# PCB.net
KiCad netlist of a schematic drawn in EAGLE
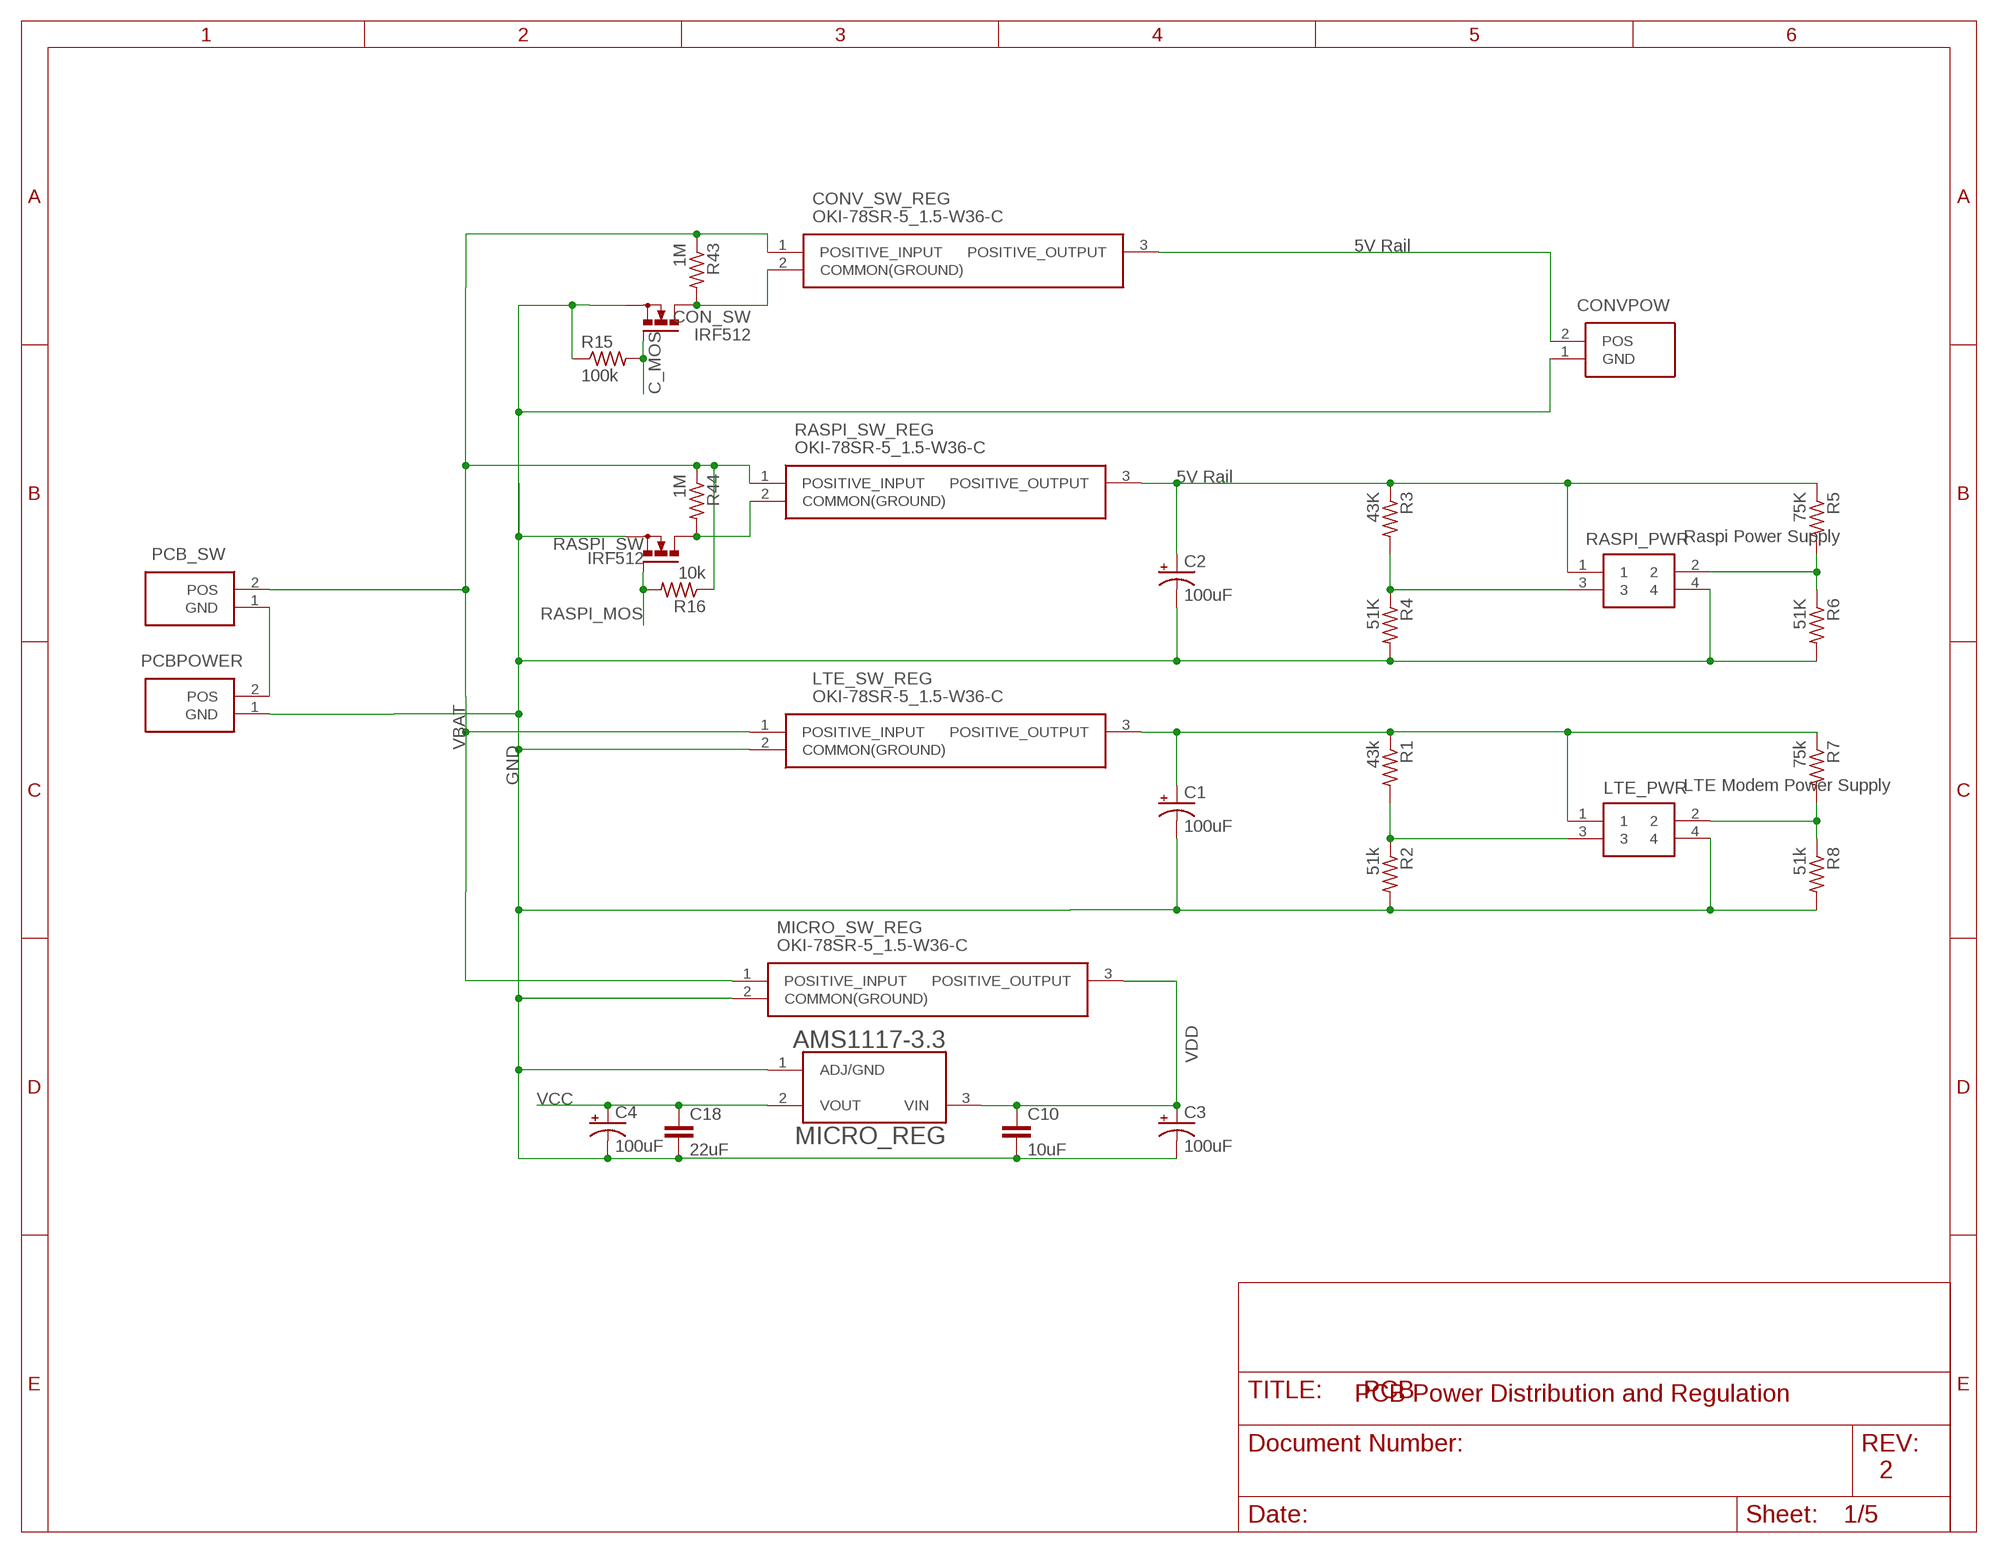
[diagram p0: schematic, sheet 1]
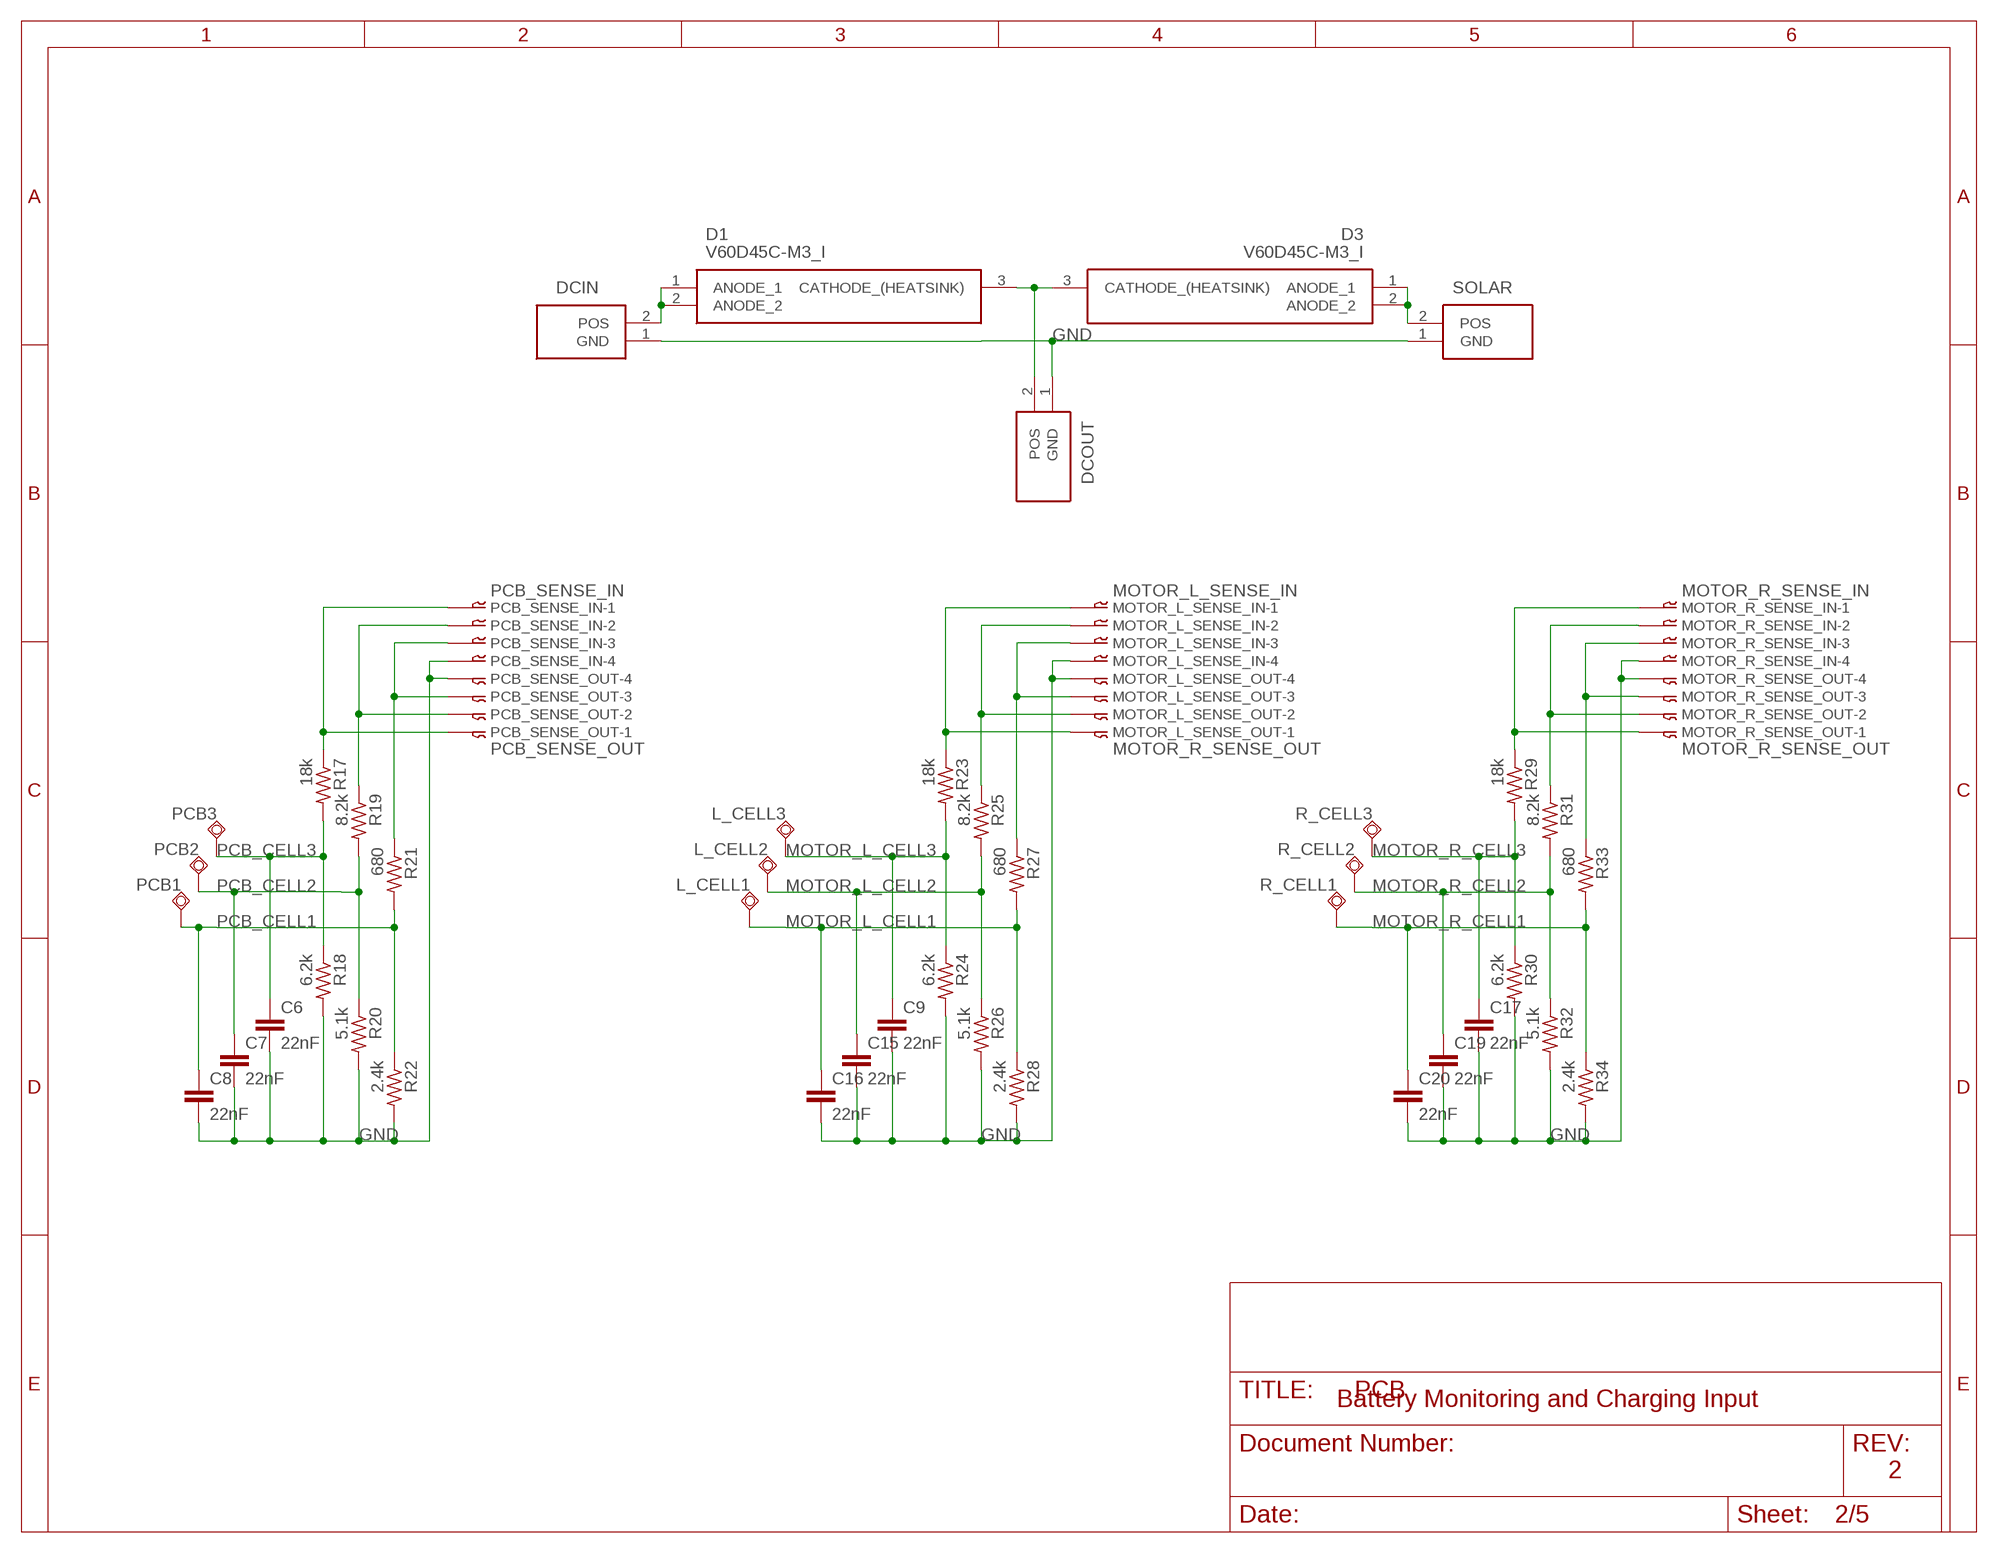
[diagram p1: schematic, sheet 2]
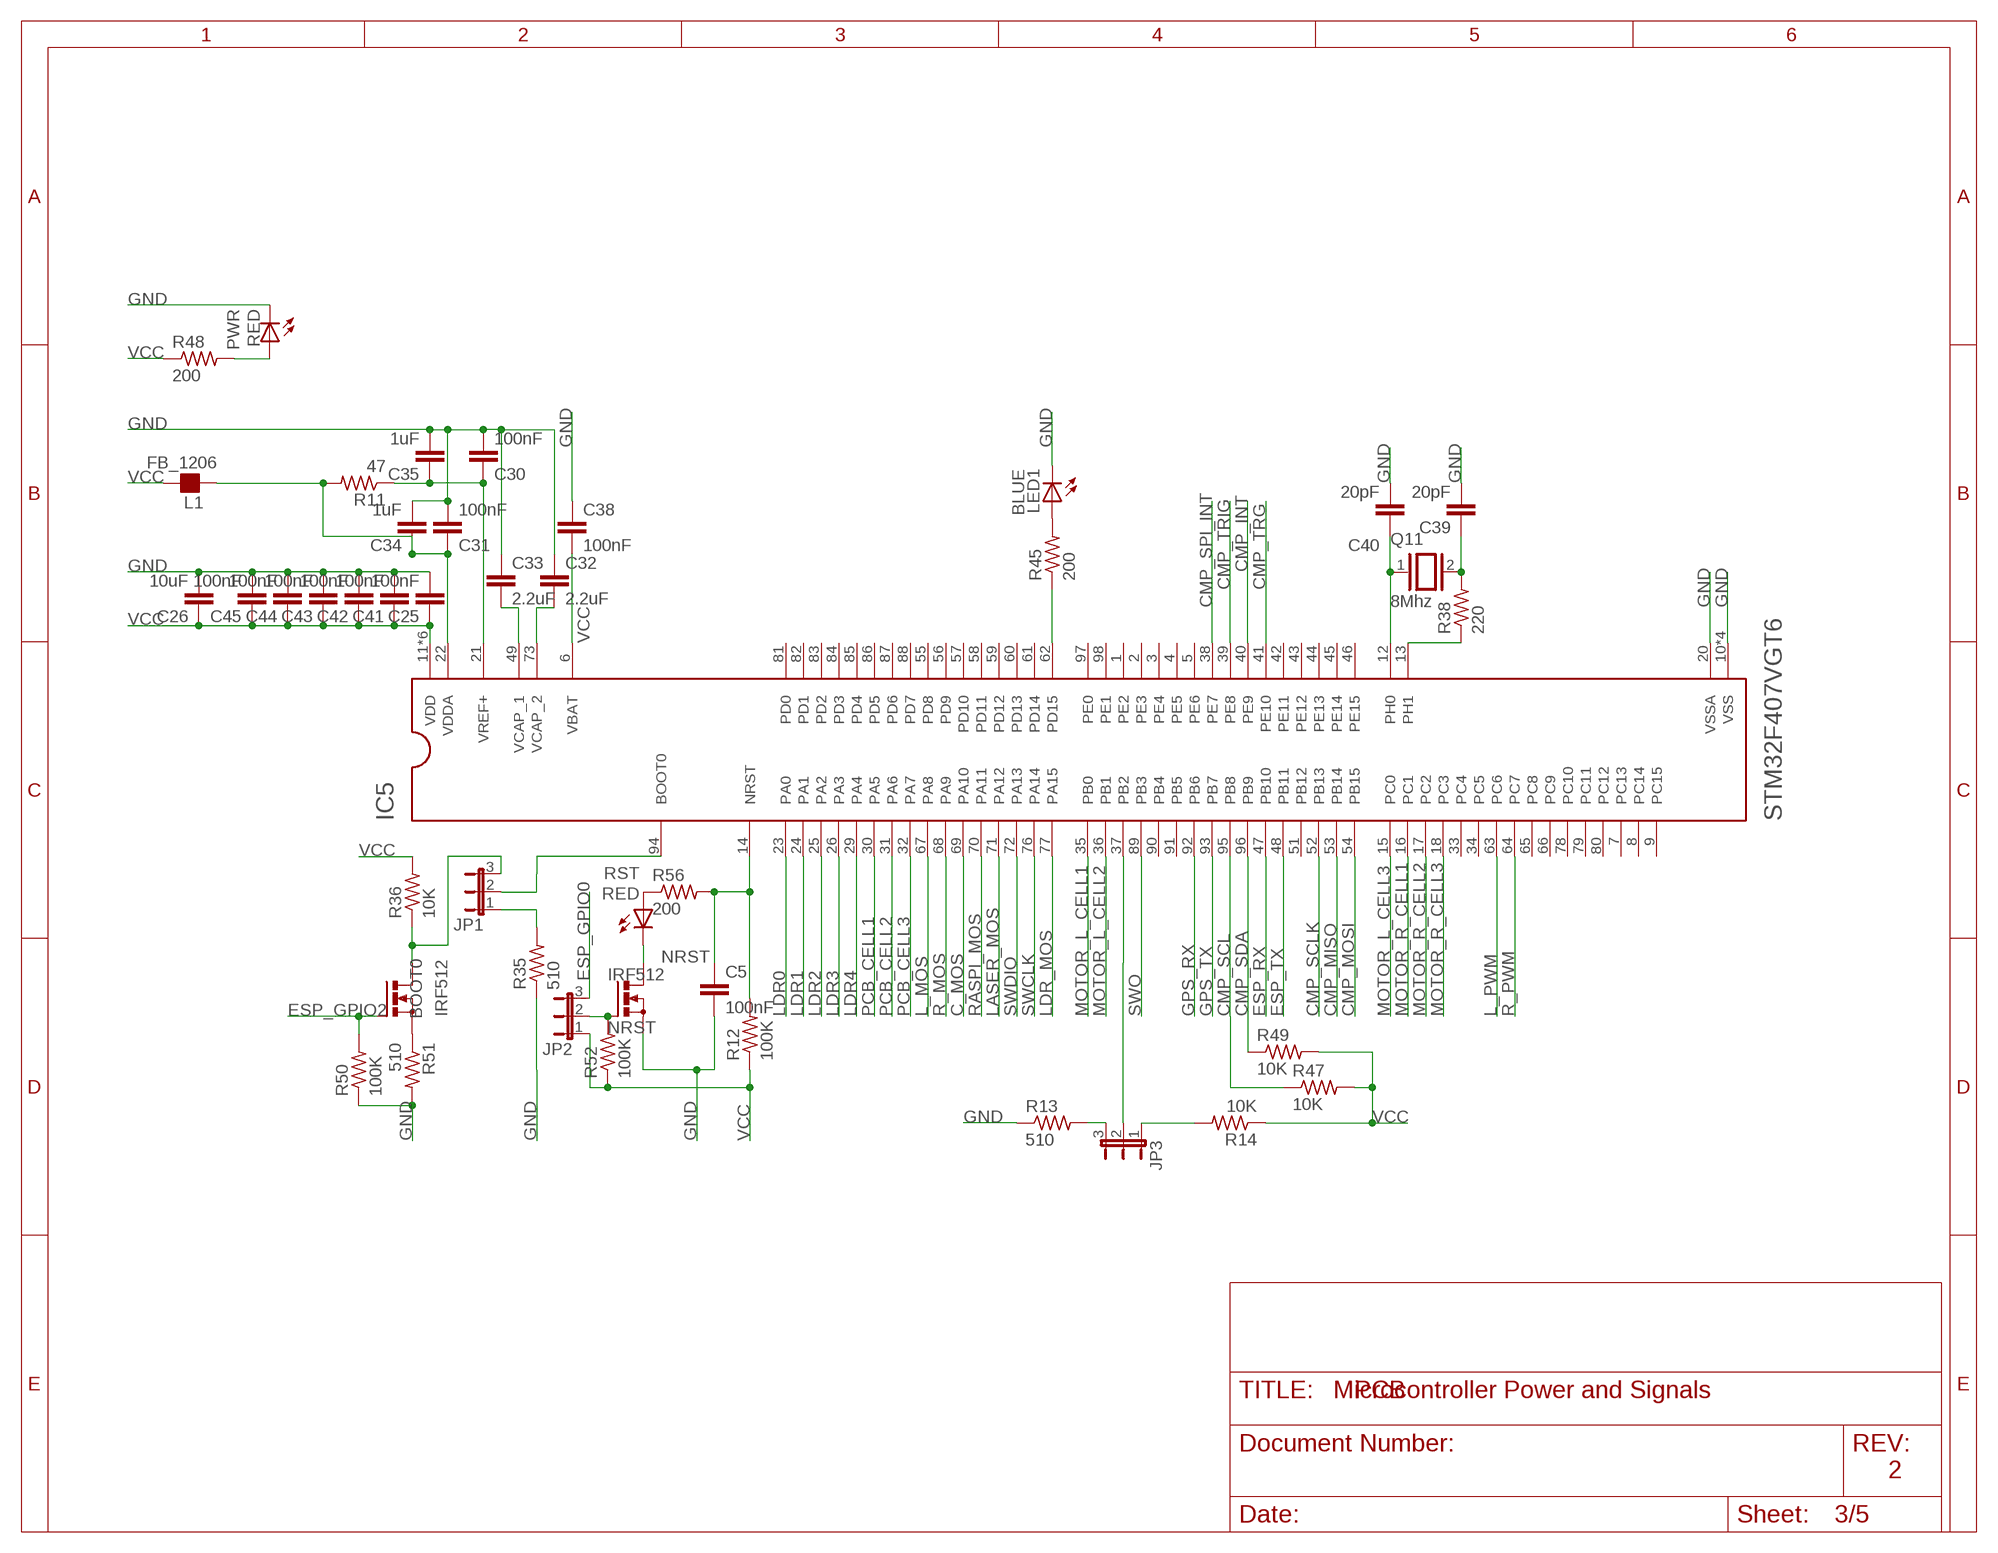
[diagram p2: schematic, sheet 3]
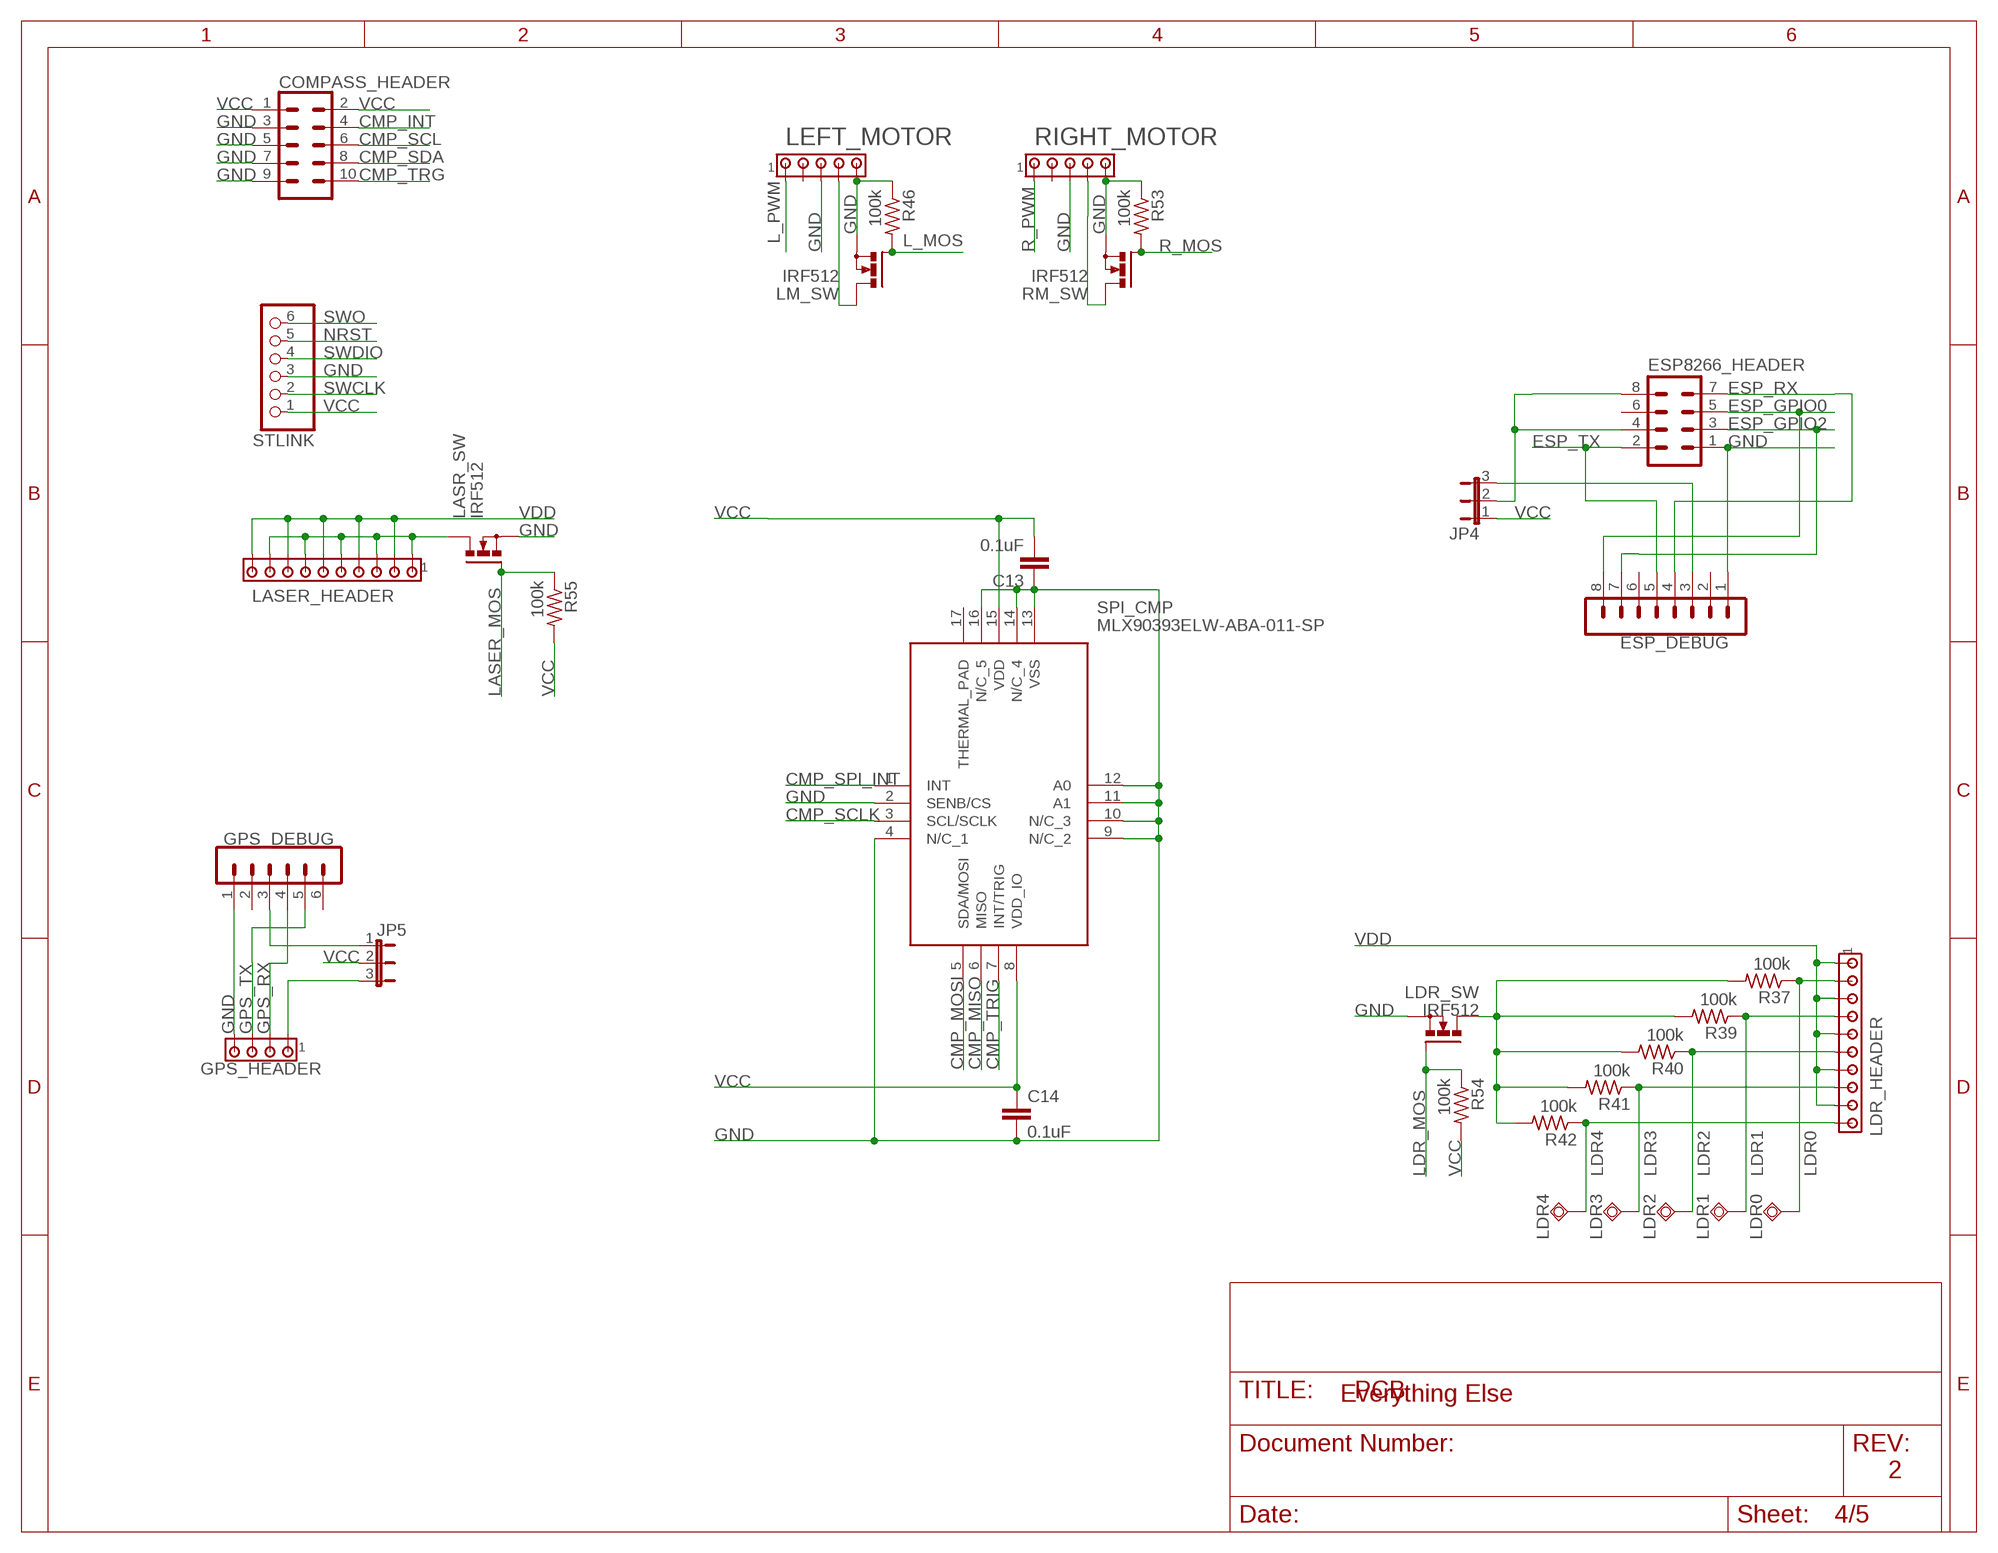
[diagram p3: schematic, sheet 4]
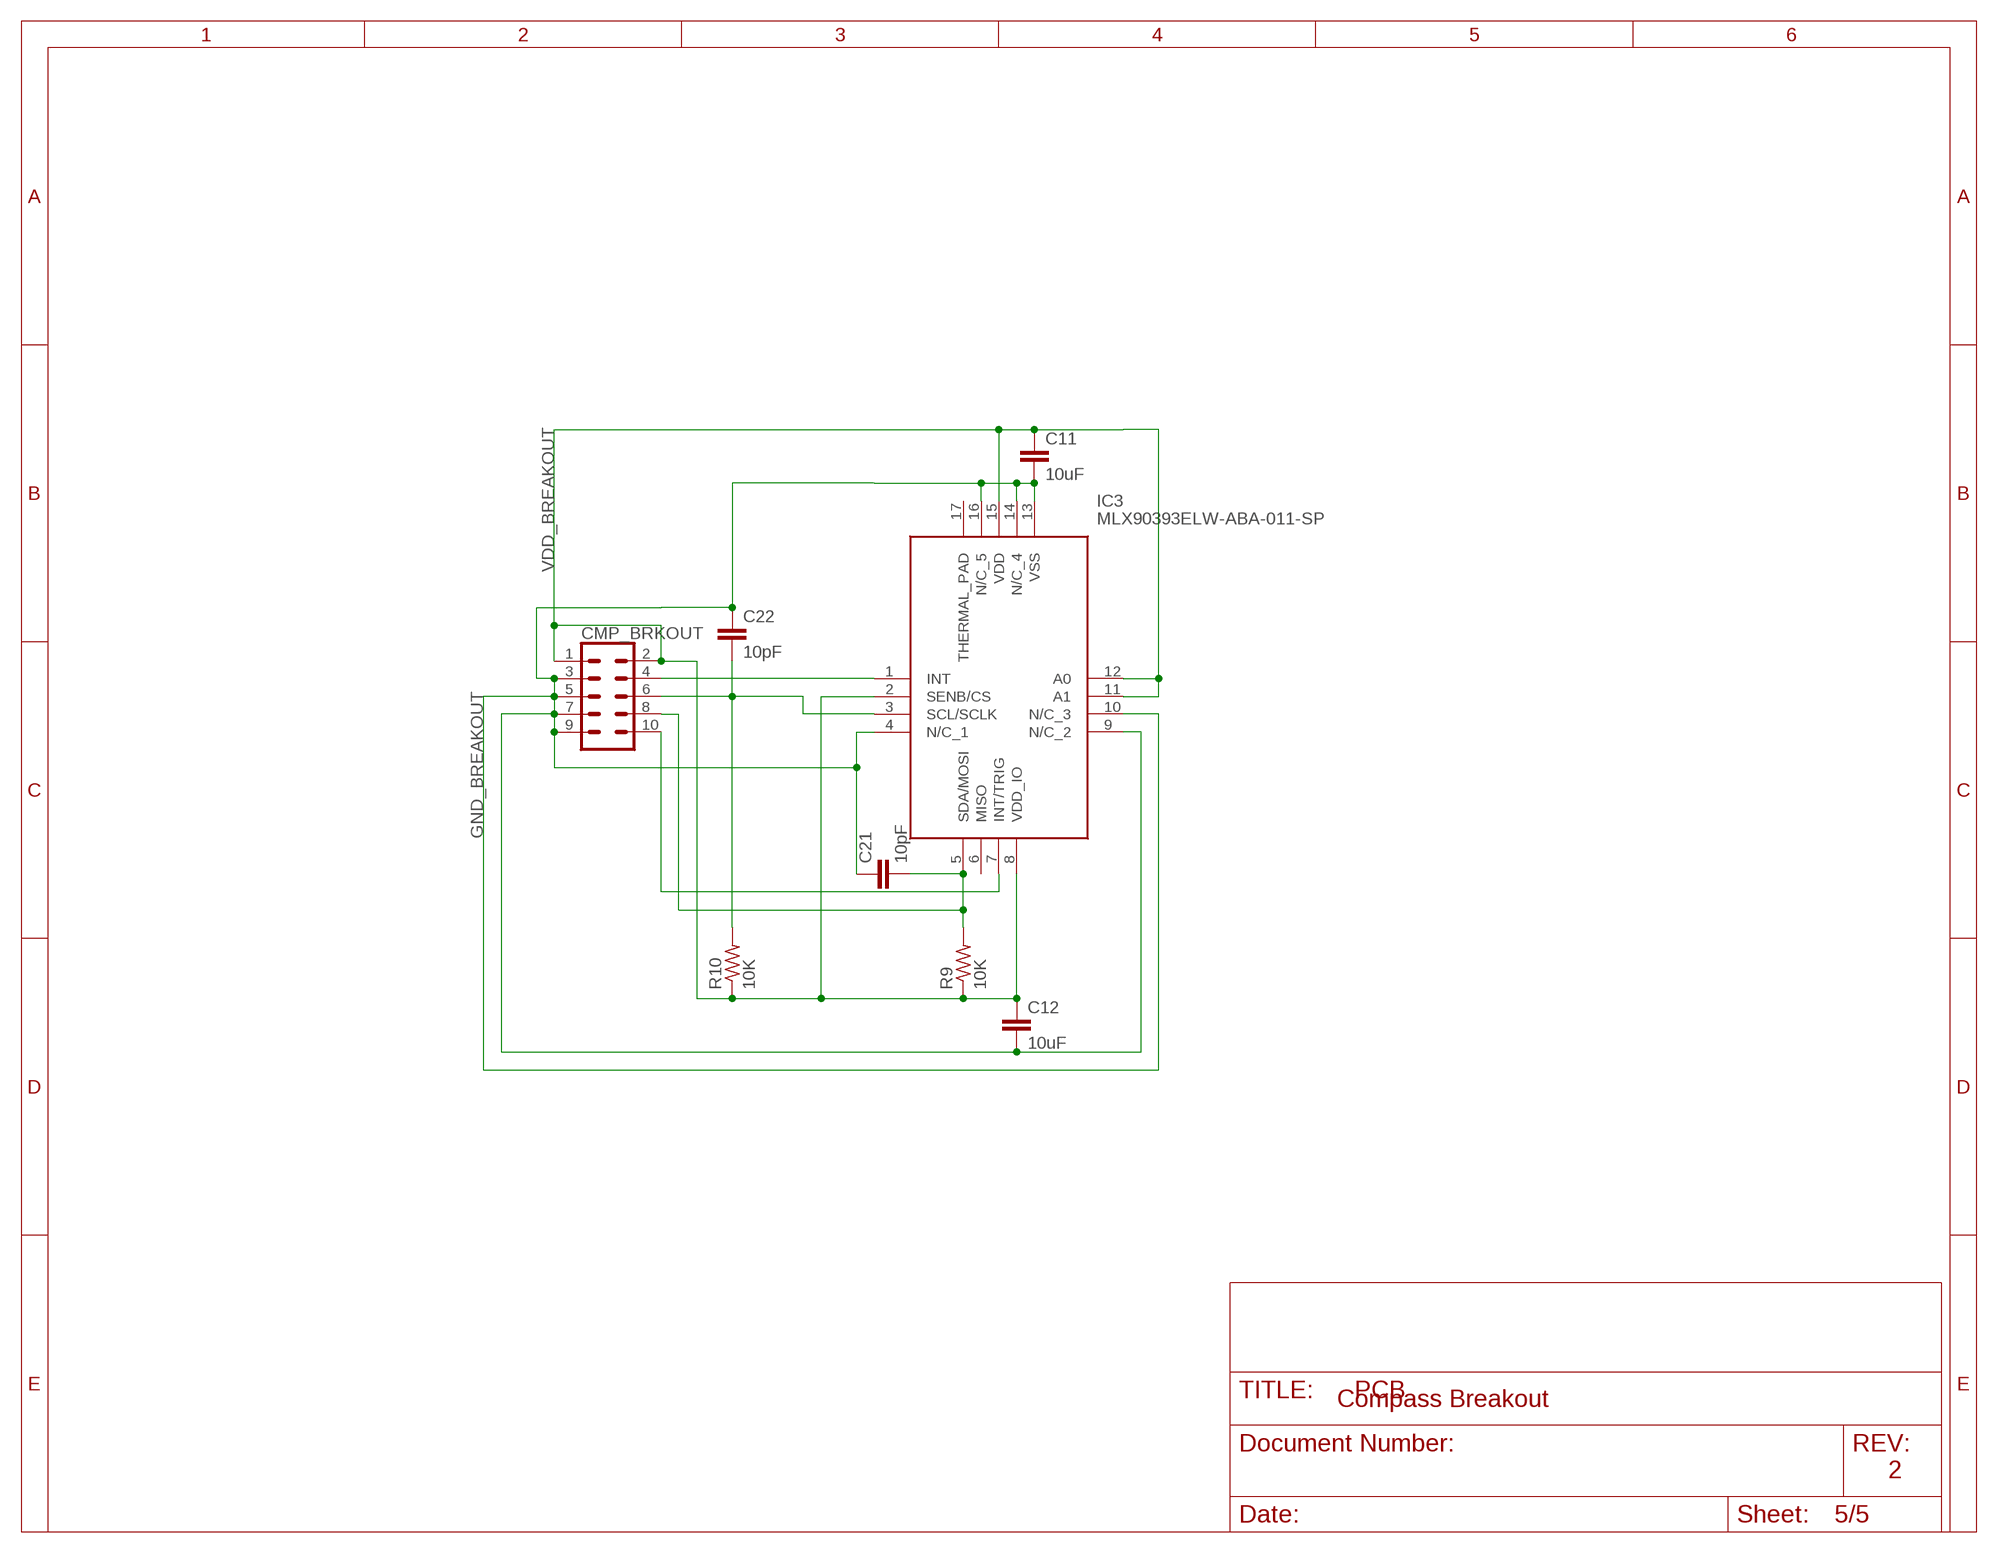
[diagram p4: schematic, sheet 5]

(export (version "E")
  (design (tool "Eeschema 10.0.6"))
  (components
    (comp (ref "C6")
      (value "22nF")
      (footprint "eagle-import:C0805")
      (libsource (lib "eagle-import") (part "C"))
    )
    (comp (ref "C7")
      (value "22nF")
      (footprint "eagle-import:C0805")
      (libsource (lib "eagle-import") (part "C"))
    )
    (comp (ref "C8")
      (value "22nF")
      (footprint "eagle-import:C0805")
      (libsource (lib "eagle-import") (part "C"))
    )
    (comp (ref "C9")
      (value "22nF")
      (footprint "eagle-import:C0805")
      (libsource (lib "eagle-import") (part "C"))
    )
    (comp (ref "C15")
      (value "22nF")
      (footprint "eagle-import:C0805")
      (libsource (lib "eagle-import") (part "C"))
    )
    (comp (ref "C16")
      (value "22nF")
      (footprint "eagle-import:C0805")
      (libsource (lib "eagle-import") (part "C"))
    )
    (comp (ref "C17")
      (value "22nF")
      (footprint "eagle-import:C0805")
      (libsource (lib "eagle-import") (part "C"))
    )
    (comp (ref "C19")
      (value "22nF")
      (footprint "eagle-import:C0805")
      (libsource (lib "eagle-import") (part "C"))
    )
    (comp (ref "C20")
      (value "22nF")
      (footprint "eagle-import:C0805")
      (libsource (lib "eagle-import") (part "C"))
    )
    (comp (ref "D1")
      (value "V60D45C-M3_I")
      (footprint "eagle-import:TO-263AC(SMPD)")
      (fields (field (name "ARROW_PART_NUMBER") "V60D45C-M3/I") (field (name "RS_PART_NUMBER") "8321024"))
      (libsource (lib "eagle-import") (part "V60D45C-M3_I"))
    )
    (comp (ref "D3")
      (value "V60D45C-M3_I")
      (footprint "eagle-import:TO-263AC(SMPD)")
      (fields (field (name "ARROW_PART_NUMBER") "V60D45C-M3/I") (field (name "RS_PART_NUMBER") "8321024"))
      (libsource (lib "eagle-import") (part "V60D45C-M3_I"))
    )
    (comp (ref "DCIN")
      (value "PRT-10474")
      (footprint "eagle-import:SHDR2W320P716_1X2_1574X813X158")
      (libsource (lib "eagle-import") (part "PRT-10474"))
    )
    (comp (ref "DCOUT")
      (value "PRT-10474")
      (footprint "eagle-import:SHDR2W320P716_1X2_1574X813X158")
      (libsource (lib "eagle-import") (part "PRT-10474"))
    )
    (comp (ref "L_CELL1")
      (value "TPSQB2,54")
      (footprint "eagle-import:B2,54")
      (libsource (lib "eagle-import") (part "TPSQB2,54"))
    )
    (comp (ref "L_CELL2")
      (value "TPSQB2,54")
      (footprint "eagle-import:B2,54")
      (libsource (lib "eagle-import") (part "TPSQB2,54"))
    )
    (comp (ref "L_CELL3")
      (value "PCB_CELL3")
      (footprint "eagle-import:B2,54")
      (libsource (lib "eagle-import") (part "TPSQB2,54"))
    )
    (comp (ref "MOTOR_L_SENSE_IN")
      (value "MOTOR_L_SENSE_IN")
      (footprint "eagle-import:B4B-XH")
      (libsource (lib "eagle-import") (part "04-JST-B4B-XH-A"))
    )
    (comp (ref "MOTOR_L_SENSE_OUT")
      (value "MOTOR_R_SENSE_OUT")
      (footprint "eagle-import:B4B-XH")
      (libsource (lib "eagle-import") (part "04-JST-B4B-XH-A"))
    )
    (comp (ref "MOTOR_R_SENSE_IN")
      (value "MOTOR_R_SENSE_IN")
      (footprint "eagle-import:B4B-XH")
      (libsource (lib "eagle-import") (part "04-JST-B4B-XH-A"))
    )
    (comp (ref "MOTOR_R_SENSE_OUT")
      (value "MOTOR_R_SENSE_OUT")
      (footprint "eagle-import:B4B-XH")
      (libsource (lib "eagle-import") (part "04-JST-B4B-XH-A"))
    )
    (comp (ref "PCB1")
      (value "TPSQB2,54")
      (footprint "eagle-import:B2,54")
      (libsource (lib "eagle-import") (part "TPSQB2,54"))
    )
    (comp (ref "PCB2")
      (value "TPSQB2,54")
      (footprint "eagle-import:B2,54")
      (libsource (lib "eagle-import") (part "TPSQB2,54"))
    )
    (comp (ref "PCB3")
      (value "PCB_CELL3")
      (footprint "eagle-import:B2,54")
      (libsource (lib "eagle-import") (part "TPSQB2,54"))
    )
    (comp (ref "PCB_SENSE_IN")
      (value "PCB_SENSE_IN")
      (footprint "eagle-import:B4B-XH")
      (libsource (lib "eagle-import") (part "04-JST-B4B-XH-A"))
    )
    (comp (ref "PCB_SENSE_OUT")
      (value "PCB_SENSE_OUT")
      (footprint "eagle-import:B4B-XH")
      (libsource (lib "eagle-import") (part "04-JST-B4B-XH-A"))
    )
    (comp (ref "R17")
      (value "18k")
      (footprint "eagle-import:R0805")
      (libsource (lib "eagle-import") (part "resistor_348_R-US_R0805"))
    )
    (comp (ref "R18")
      (value "6.2k")
      (footprint "eagle-import:R0805")
      (libsource (lib "eagle-import") (part "resistor_348_R-US_R0805"))
    )
    (comp (ref "R19")
      (value "8.2k")
      (footprint "eagle-import:R0805")
      (libsource (lib "eagle-import") (part "resistor_348_R-US_R0805"))
    )
    (comp (ref "R20")
      (value "5.1k")
      (footprint "eagle-import:R0805")
      (libsource (lib "eagle-import") (part "resistor_348_R-US_R0805"))
    )
    (comp (ref "R21")
      (value "680")
      (footprint "eagle-import:R0805")
      (libsource (lib "eagle-import") (part "resistor_348_R-US_R0805"))
    )
    (comp (ref "R22")
      (value "2.4k")
      (footprint "eagle-import:R0805")
      (libsource (lib "eagle-import") (part "resistor_348_R-US_R0805"))
    )
    (comp (ref "R23")
      (value "18k")
      (footprint "eagle-import:R0805")
      (libsource (lib "eagle-import") (part "resistor_348_R-US_R0805"))
    )
    (comp (ref "R24")
      (value "6.2k")
      (footprint "eagle-import:R0805")
      (libsource (lib "eagle-import") (part "resistor_348_R-US_R0805"))
    )
    (comp (ref "R25")
      (value "8.2k")
      (footprint "eagle-import:R0805")
      (libsource (lib "eagle-import") (part "resistor_348_R-US_R0805"))
    )
    (comp (ref "R26")
      (value "5.1k")
      (footprint "eagle-import:R0805")
      (libsource (lib "eagle-import") (part "resistor_348_R-US_R0805"))
    )
    (comp (ref "R27")
      (value "680")
      (footprint "eagle-import:R0805")
      (libsource (lib "eagle-import") (part "resistor_348_R-US_R0805"))
    )
    (comp (ref "R28")
      (value "2.4k")
      (footprint "eagle-import:R0805")
      (libsource (lib "eagle-import") (part "resistor_348_R-US_R0805"))
    )
    (comp (ref "R29")
      (value "18k")
      (footprint "eagle-import:R0805")
      (libsource (lib "eagle-import") (part "resistor_348_R-US_R0805"))
    )
    (comp (ref "R30")
      (value "6.2k")
      (footprint "eagle-import:R0805")
      (libsource (lib "eagle-import") (part "resistor_348_R-US_R0805"))
    )
    (comp (ref "R31")
      (value "8.2k")
      (footprint "eagle-import:R0805")
      (libsource (lib "eagle-import") (part "resistor_348_R-US_R0805"))
    )
    (comp (ref "R32")
      (value "5.1k")
      (footprint "eagle-import:R0805")
      (libsource (lib "eagle-import") (part "resistor_348_R-US_R0805"))
    )
    (comp (ref "R33")
      (value "680")
      (footprint "eagle-import:R0805")
      (libsource (lib "eagle-import") (part "resistor_348_R-US_R0805"))
    )
    (comp (ref "R34")
      (value "2.4k")
      (footprint "eagle-import:R0805")
      (libsource (lib "eagle-import") (part "resistor_348_R-US_R0805"))
    )
    (comp (ref "R_CELL1")
      (value "TPSQB2,54")
      (footprint "eagle-import:B2,54")
      (libsource (lib "eagle-import") (part "TPSQB2,54"))
    )
    (comp (ref "R_CELL2")
      (value "TPSQB2,54")
      (footprint "eagle-import:B2,54")
      (libsource (lib "eagle-import") (part "TPSQB2,54"))
    )
    (comp (ref "R_CELL3")
      (value "PCB_CELL3")
      (footprint "eagle-import:B2,54")
      (libsource (lib "eagle-import") (part "TPSQB2,54"))
    )
    (comp (ref "SOLAR")
      (value "PRT-10474")
      (footprint "eagle-import:SHDR2W320P716_1X2_1574X813X158")
      (libsource (lib "eagle-import") (part "PRT-10474"))
    )
    (comp (ref "BOOT0")
      (value "IRF512")
      (footprint "eagle-import:TO220BV")
      (libsource (lib "eagle-import") (part "IRF512"))
    )
    (comp (ref "C5")
      (value "100nF")
      (footprint "eagle-import:C0805")
      (libsource (lib "eagle-import") (part "C-EUC0805"))
    )
    (comp (ref "C25")
      (value "100nF")
      (footprint "eagle-import:C0805")
      (libsource (lib "eagle-import") (part "C-EUC0805"))
    )
    (comp (ref "C26")
      (value "10uF")
      (footprint "eagle-import:C0805")
      (libsource (lib "eagle-import") (part "C-EUC0805"))
    )
    (comp (ref "C30")
      (value "100nF")
      (footprint "eagle-import:C0805")
      (libsource (lib "eagle-import") (part "C-EUC0805"))
    )
    (comp (ref "C31")
      (value "100nF")
      (footprint "eagle-import:C0805")
      (libsource (lib "eagle-import") (part "C-EUC0805"))
    )
    (comp (ref "C32")
      (value "2.2uF")
      (footprint "eagle-import:C0805")
      (libsource (lib "eagle-import") (part "C-EUC0805"))
    )
    (comp (ref "C33")
      (value "2.2uF")
      (footprint "eagle-import:C0805")
      (libsource (lib "eagle-import") (part "C-EUC0805"))
    )
    (comp (ref "C34")
      (value "1uF")
      (footprint "eagle-import:C0805")
      (libsource (lib "eagle-import") (part "C-EUC0805"))
    )
    (comp (ref "C35")
      (value "1uF")
      (footprint "eagle-import:C0805")
      (libsource (lib "eagle-import") (part "C-EUC0805"))
    )
    (comp (ref "C38")
      (value "100nF")
      (footprint "eagle-import:C0805")
      (libsource (lib "eagle-import") (part "C-EUC0805"))
    )
    (comp (ref "C39")
      (value "20pF")
      (footprint "eagle-import:C0805")
      (libsource (lib "eagle-import") (part "C-EUC0805"))
    )
    (comp (ref "C40")
      (value "20pF")
      (footprint "eagle-import:C0805")
      (libsource (lib "eagle-import") (part "C-EUC0805"))
    )
    (comp (ref "C41")
      (value "100nF")
      (footprint "eagle-import:C0805")
      (libsource (lib "eagle-import") (part "C-EUC0805"))
    )
    (comp (ref "C42")
      (value "100nF")
      (footprint "eagle-import:C0805")
      (libsource (lib "eagle-import") (part "C-EUC0805"))
    )
    (comp (ref "C43")
      (value "100nF")
      (footprint "eagle-import:C0805")
      (libsource (lib "eagle-import") (part "C-EUC0805"))
    )
    (comp (ref "C44")
      (value "100nF")
      (footprint "eagle-import:C0805")
      (libsource (lib "eagle-import") (part "C-EUC0805"))
    )
    (comp (ref "C45")
      (value "100nF")
      (footprint "eagle-import:C0805")
      (libsource (lib "eagle-import") (part "C-EUC0805"))
    )
    (comp (ref "IC5")
      (value "STM32F407VGT6")
      (footprint "eagle-import:QFP50P1600X1600X160-100N")
      (fields (field (name "MF") "STMicroelectronics"))
      (libsource (lib "eagle-import") (part "STM32F407VGT6"))
    )
    (comp (ref "JP1")
      (value "JP2E")
      (footprint "eagle-import:JP2")
      (libsource (lib "eagle-import") (part "JP2E"))
    )
    (comp (ref "JP2")
      (value "JP2E")
      (footprint "eagle-import:JP2")
      (libsource (lib "eagle-import") (part "JP2E"))
    )
    (comp (ref "JP3")
      (value "JP2E")
      (footprint "eagle-import:JP2")
      (libsource (lib "eagle-import") (part "JP2E"))
    )
    (comp (ref "L1")
      (value "FB_1206")
      (footprint "eagle-import:L1206")
      (libsource (lib "eagle-import") (part "FB_1206"))
    )
    (comp (ref "LED1")
      (value "BLUE")
      (footprint "eagle-import:CHIPLED_0805")
      (libsource (lib "eagle-import") (part "LEDCHIPLED_0805"))
    )
    (comp (ref "NRST")
      (value "IRF512")
      (footprint "eagle-import:TO220BV")
      (libsource (lib "eagle-import") (part "IRF512"))
    )
    (comp (ref "PWR")
      (value "RED")
      (footprint "eagle-import:CHIPLED_0805")
      (libsource (lib "eagle-import") (part "LEDCHIPLED_0805"))
    )
    (comp (ref "Q11")
      (value "8Mhz")
      (footprint "eagle-import:QS")
      (libsource (lib "eagle-import") (part "XTAL/S"))
    )
    (comp (ref "R11")
      (value "47")
      (footprint "eagle-import:R0805")
      (libsource (lib "eagle-import") (part "R-US_R0805"))
    )
    (comp (ref "R12")
      (value "100K")
      (footprint "eagle-import:R0805")
      (libsource (lib "eagle-import") (part "R-US_R0805"))
    )
    (comp (ref "R13")
      (value "510")
      (footprint "eagle-import:R0805")
      (libsource (lib "eagle-import") (part "R-US_R0805"))
    )
    (comp (ref "R14")
      (value "10K")
      (footprint "eagle-import:R0805")
      (libsource (lib "eagle-import") (part "R-US_R0805"))
    )
    (comp (ref "R35")
      (value "510")
      (footprint "eagle-import:R0805")
      (libsource (lib "eagle-import") (part "R-US_R0805"))
    )
    (comp (ref "R36")
      (value "10K")
      (footprint "eagle-import:R0805")
      (libsource (lib "eagle-import") (part "R-US_R0805"))
    )
    (comp (ref "R38")
      (value "220")
      (footprint "eagle-import:R0805")
      (libsource (lib "eagle-import") (part "R-US_R0805"))
    )
    (comp (ref "R45")
      (value "200")
      (footprint "eagle-import:R0805")
      (libsource (lib "eagle-import") (part "R-US_R0805"))
    )
    (comp (ref "R47")
      (value "10K")
      (footprint "eagle-import:R0805")
      (libsource (lib "eagle-import") (part "R-US_R0805"))
    )
    (comp (ref "R48")
      (value "200")
      (footprint "eagle-import:R0805")
      (libsource (lib "eagle-import") (part "R-US_R0805"))
    )
    (comp (ref "R49")
      (value "10K")
      (footprint "eagle-import:R0805")
      (libsource (lib "eagle-import") (part "R-US_R0805"))
    )
    (comp (ref "R50")
      (value "100K")
      (footprint "eagle-import:R0805")
      (libsource (lib "eagle-import") (part "R-US_R0805"))
    )
    (comp (ref "R51")
      (value "510")
      (footprint "eagle-import:R0805")
      (libsource (lib "eagle-import") (part "R-US_R0805"))
    )
    (comp (ref "R52")
      (value "100K")
      (footprint "eagle-import:R0805")
      (libsource (lib "eagle-import") (part "R-US_R0805"))
    )
    (comp (ref "R56")
      (value "200")
      (footprint "eagle-import:R0805")
      (libsource (lib "eagle-import") (part "R-US_R0805"))
    )
    (comp (ref "RST")
      (value "RED")
      (footprint "eagle-import:CHIPLED_0805")
      (libsource (lib "eagle-import") (part "LEDCHIPLED_0805"))
    )
    (comp (ref "C11")
      (value "10uF")
      (footprint "eagle-import:C1206")
      (libsource (lib "eagle-import") (part "resistor_348_C-EUC1206"))
    )
    (comp (ref "C12")
      (value "10uF")
      (footprint "eagle-import:C1206")
      (libsource (lib "eagle-import") (part "resistor_348_C-EUC1206"))
    )
    (comp (ref "C21")
      (value "10pF")
      (footprint "eagle-import:C1206")
      (libsource (lib "eagle-import") (part "resistor_348_C-EUC1206"))
    )
    (comp (ref "C22")
      (value "10pF")
      (footprint "eagle-import:C1206")
      (libsource (lib "eagle-import") (part "resistor_348_C-EUC1206"))
    )
    (comp (ref "CMP_BRKOUT")
      (value "CONN_05X2SHD")
      (footprint "eagle-import:2X5-SHROUDED")
      (libsource (lib "eagle-import") (part "CONN_05X2SHD"))
    )
    (comp (ref "IC3")
      (value "MLX90393ELW-ABA-011-SP")
      (footprint "eagle-import:QFN50P300X300X100-17N")
      (libsource (lib "eagle-import") (part "MLX90393ELW-ABA-011-SP"))
    )
    (comp (ref "R9")
      (value "10K")
      (footprint "eagle-import:R1206")
      (libsource (lib "eagle-import") (part "resistor_348_R-US_R1206"))
    )
    (comp (ref "R10")
      (value "10K")
      (footprint "eagle-import:R1206")
      (libsource (lib "eagle-import") (part "resistor_348_R-US_R1206"))
    )
    (comp (ref "C13")
      (value "0.1uF")
      (footprint "eagle-import:C1206")
      (libsource (lib "eagle-import") (part "resistor_348_C-EUC1206"))
    )
    (comp (ref "C14")
      (value "0.1uF")
      (footprint "eagle-import:C1206")
      (libsource (lib "eagle-import") (part "resistor_348_C-EUC1206"))
    )
    (comp (ref "COMPASS_HEADER")
      (value "CONN_05X2SHD")
      (footprint "eagle-import:2X5-SHROUDED")
      (libsource (lib "eagle-import") (part "CONN_05X2SHD"))
    )
    (comp (ref "ESP8266_HEADER")
      (value "MA04-2")
      (footprint "eagle-import:MA04-2")
      (libsource (lib "eagle-import") (part "MA04-2"))
    )
    (comp (ref "ESP_DEBUG")
      (value "MA08-1")
      (footprint "eagle-import:MA08-1")
      (libsource (lib "eagle-import") (part "MA08-1"))
    )
    (comp (ref "GPS_DEBUG")
      (value "MA06-1")
      (footprint "eagle-import:MA06-1")
      (libsource (lib "eagle-import") (part "MA06-1"))
    )
    (comp (ref "GPS_HEADER")
      (value "MTA04-100")
      (footprint "eagle-import:10X04MTA")
      (libsource (lib "eagle-import") (part "MTA04-100"))
    )
    (comp (ref "JP4")
      (value "JP2E")
      (footprint "eagle-import:JP2")
      (libsource (lib "eagle-import") (part "JP2E"))
    )
    (comp (ref "JP5")
      (value "JP2E")
      (footprint "eagle-import:JP2")
      (libsource (lib "eagle-import") (part "JP2E"))
    )
    (comp (ref "LASER_HEADER")
      (value "MTA10-100")
      (footprint "eagle-import:10X10MTA")
      (libsource (lib "eagle-import") (part "MTA10-100"))
    )
    (comp (ref "LASR_SW")
      (value "IRF512")
      (footprint "eagle-import:TO220BV")
      (libsource (lib "eagle-import") (part "IRF512"))
    )
    (comp (ref "LDR0")
      (value "TPSQB2,54")
      (footprint "eagle-import:B2,54")
      (libsource (lib "eagle-import") (part "TPSQB2,54"))
    )
    (comp (ref "LDR1")
      (value "TPSQB2,54")
      (footprint "eagle-import:B2,54")
      (libsource (lib "eagle-import") (part "TPSQB2,54"))
    )
    (comp (ref "LDR2")
      (value "TPSQB2,54")
      (footprint "eagle-import:B2,54")
      (libsource (lib "eagle-import") (part "TPSQB2,54"))
    )
    (comp (ref "LDR3")
      (value "TPSQB2,54")
      (footprint "eagle-import:B2,54")
      (libsource (lib "eagle-import") (part "TPSQB2,54"))
    )
    (comp (ref "LDR4")
      (value "TPSQB2,54")
      (footprint "eagle-import:B2,54")
      (libsource (lib "eagle-import") (part "TPSQB2,54"))
    )
    (comp (ref "LDR_HEADER")
      (value "MTA10-100")
      (footprint "eagle-import:10X10MTA")
      (libsource (lib "eagle-import") (part "MTA10-100"))
    )
    (comp (ref "LDR_SW")
      (value "IRF512")
      (footprint "eagle-import:TO220BV")
      (libsource (lib "eagle-import") (part "IRF512"))
    )
    (comp (ref "LEFT_MOTOR")
      (value "MTA05-100")
      (footprint "eagle-import:1X05MTA")
      (libsource (lib "eagle-import") (part "MTA05-100"))
    )
    (comp (ref "LM_SW")
      (value "IRF512")
      (footprint "eagle-import:TO220BV")
      (libsource (lib "eagle-import") (part "IRF512"))
    )
    (comp (ref "R37")
      (value "100k")
      (footprint "eagle-import:R1206")
      (libsource (lib "eagle-import") (part "resistor_348_R-US_R1206"))
    )
    (comp (ref "R39")
      (value "100k")
      (footprint "eagle-import:R1206")
      (libsource (lib "eagle-import") (part "resistor_348_R-US_R1206"))
    )
    (comp (ref "R40")
      (value "100k")
      (footprint "eagle-import:R1206")
      (libsource (lib "eagle-import") (part "resistor_348_R-US_R1206"))
    )
    (comp (ref "R41")
      (value "100k")
      (footprint "eagle-import:R1206")
      (libsource (lib "eagle-import") (part "resistor_348_R-US_R1206"))
    )
    (comp (ref "R42")
      (value "100k")
      (footprint "eagle-import:R1206")
      (libsource (lib "eagle-import") (part "resistor_348_R-US_R1206"))
    )
    (comp (ref "R46")
      (value "100k")
      (footprint "eagle-import:R1206")
      (libsource (lib "eagle-import") (part "resistor_348_R-US_R1206"))
    )
    (comp (ref "R53")
      (value "100k")
      (footprint "eagle-import:R1206")
      (libsource (lib "eagle-import") (part "resistor_348_R-US_R1206"))
    )
    (comp (ref "R54")
      (value "100k")
      (footprint "eagle-import:R1206")
      (libsource (lib "eagle-import") (part "resistor_348_R-US_R1206"))
    )
    (comp (ref "R55")
      (value "100k")
      (footprint "eagle-import:R1206")
      (libsource (lib "eagle-import") (part "resistor_348_R-US_R1206"))
    )
    (comp (ref "RIGHT_MOTOR")
      (value "MTA05-100")
      (footprint "eagle-import:1X05MTA")
      (libsource (lib "eagle-import") (part "MTA05-100"))
    )
    (comp (ref "RM_SW")
      (value "IRF512")
      (footprint "eagle-import:TO220BV")
      (libsource (lib "eagle-import") (part "IRF512"))
    )
    (comp (ref "SPI_CMP")
      (value "MLX90393ELW-ABA-011-SP")
      (footprint "eagle-import:QFN50P300X300X100-17N")
      (libsource (lib "eagle-import") (part "MLX90393ELW-ABA-011-SP"))
    )
    (comp (ref "STLINK")
      (value "PINHD-1X6")
      (footprint "eagle-import:1X06")
      (libsource (lib "eagle-import") (part "PINHD-1X6"))
    )
    (comp (ref "C1")
      (value "100uF")
      (footprint "eagle-import:140CLH-0810")
      (libsource (lib "eagle-import") (part "CPOL-US140CLH-0810"))
    )
    (comp (ref "C2")
      (value "100uF")
      (footprint "eagle-import:140CLH-0810")
      (libsource (lib "eagle-import") (part "CPOL-US140CLH-0810"))
    )
    (comp (ref "C3")
      (value "100uF")
      (footprint "eagle-import:140CLH-0810")
      (libsource (lib "eagle-import") (part "CPOL-US140CLH-0810"))
    )
    (comp (ref "C4")
      (value "100uF")
      (footprint "eagle-import:140CLH-0810")
      (libsource (lib "eagle-import") (part "CPOL-US140CLH-0810"))
    )
    (comp (ref "C10")
      (value "10uF")
      (footprint "eagle-import:C0805")
      (libsource (lib "eagle-import") (part "resistor_348_C-EUC0805"))
    )
    (comp (ref "C18")
      (value "22uF")
      (footprint "eagle-import:C0805")
      (libsource (lib "eagle-import") (part "resistor_348_C-EUC0805"))
    )
    (comp (ref "CONVPOW")
      (value "PRT-10474")
      (footprint "eagle-import:SHDR2W320P716_1X2_1574X813X158")
      (libsource (lib "eagle-import") (part "PRT-10474"))
    )
    (comp (ref "CONV_SW_REG")
      (value "OKI-78SR-5_1.5-W36-C")
      (footprint "eagle-import:OKI-78SR")
      (fields
        (field (name "ARROW_PART_NUMBER") "OKI-78SR-5/1.5-W36-C")
        (field (name "RS_PART_NUMBER") "1736928")
      )
      (libsource (lib "eagle-import") (part "OKI-78SR-5_1.5-W36-C"))
    )
    (comp (ref "CON_SW")
      (value "IRF512")
      (footprint "eagle-import:TO220BV")
      (libsource (lib "eagle-import") (part "IRF512"))
    )
    (comp (ref "LTE_PWR")
      (value "LTE Modem Power Supply")
      (footprint "eagle-import:105057-0001")
      (fields (field (name "ARROW_PART_NUMBER") "105057-0001") (field (name "RS_PART_NUMBER") "8967579"))
      (libsource (lib "eagle-import") (part "105057-0001"))
    )
    (comp (ref "LTE_SW_REG")
      (value "OKI-78SR-5_1.5-W36-C")
      (footprint "eagle-import:OKI-78SR")
      (fields
        (field (name "ARROW_PART_NUMBER") "OKI-78SR-5/1.5-W36-C")
        (field (name "RS_PART_NUMBER") "1736928")
      )
      (libsource (lib "eagle-import") (part "OKI-78SR-5_1.5-W36-C"))
    )
    (comp (ref "MICRO_REG")
      (value "AMS1117-3.3")
      (footprint "eagle-import:SOT229P700X180-4N")
      (fields (field (name "MF") "Advanced Monolithic Systems"))
      (libsource (lib "eagle-import") (part "AMS1117-3.3"))
    )
    (comp (ref "MICRO_SW_REG")
      (value "OKI-78SR-5_1.5-W36-C")
      (footprint "eagle-import:OKI-78SR")
      (fields
        (field (name "ARROW_PART_NUMBER") "OKI-78SR-5/1.5-W36-C")
        (field (name "RS_PART_NUMBER") "1736928")
      )
      (libsource (lib "eagle-import") (part "OKI-78SR-5_1.5-W36-C"))
    )
    (comp (ref "PCBPOWER")
      (value "PRT-10474")
      (footprint "eagle-import:SHDR2W320P716_1X2_1574X813X158")
      (libsource (lib "eagle-import") (part "PRT-10474"))
    )
    (comp (ref "PCB_SW")
      (value "PRT-10474")
      (footprint "eagle-import:SHDR2W320P716_1X2_1574X813X158")
      (libsource (lib "eagle-import") (part "PRT-10474"))
    )
    (comp (ref "R1")
      (value "43k")
      (footprint "eagle-import:R0805")
      (libsource (lib "eagle-import") (part "resistor_348_R-US_R0805"))
    )
    (comp (ref "R2")
      (value "51k")
      (footprint "eagle-import:R0805")
      (libsource (lib "eagle-import") (part "resistor_348_R-US_R0805"))
    )
    (comp (ref "R3")
      (value "43K")
      (footprint "eagle-import:R0805")
      (libsource (lib "eagle-import") (part "resistor_348_R-US_R0805"))
    )
    (comp (ref "R4")
      (value "51K")
      (footprint "eagle-import:R0805")
      (libsource (lib "eagle-import") (part "resistor_348_R-US_R0805"))
    )
    (comp (ref "R5")
      (value "75K")
      (footprint "eagle-import:R0805")
      (libsource (lib "eagle-import") (part "resistor_348_R-US_R0805"))
    )
    (comp (ref "R6")
      (value "51K")
      (footprint "eagle-import:R0805")
      (libsource (lib "eagle-import") (part "resistor_348_R-US_R0805"))
    )
    (comp (ref "R7")
      (value "75k")
      (footprint "eagle-import:R0805")
      (libsource (lib "eagle-import") (part "resistor_348_R-US_R0805"))
    )
    (comp (ref "R8")
      (value "51k")
      (footprint "eagle-import:R0805")
      (libsource (lib "eagle-import") (part "resistor_348_R-US_R0805"))
    )
    (comp (ref "R15")
      (value "100k")
      (footprint "eagle-import:R0805")
      (libsource (lib "eagle-import") (part "resistor_348_R-US_R0805"))
    )
    (comp (ref "R16")
      (value "10k")
      (footprint "eagle-import:R0805")
      (libsource (lib "eagle-import") (part "resistor_348_R-US_R0805"))
    )
    (comp (ref "R43")
      (value "1M")
      (footprint "eagle-import:R0805")
      (libsource (lib "eagle-import") (part "resistor_348_R-US_R0805"))
    )
    (comp (ref "R44")
      (value "1M")
      (footprint "eagle-import:R0805")
      (libsource (lib "eagle-import") (part "resistor_348_R-US_R0805"))
    )
    (comp (ref "RASPI_PWR")
      (value "Raspi Power Supply")
      (footprint "eagle-import:105057-0001")
      (fields (field (name "ARROW_PART_NUMBER") "105057-0001") (field (name "RS_PART_NUMBER") "8967579"))
      (libsource (lib "eagle-import") (part "105057-0001"))
    )
    (comp (ref "RASPI_SW")
      (value "IRF512")
      (footprint "eagle-import:TO220BV")
      (libsource (lib "eagle-import") (part "IRF512"))
    )
    (comp (ref "RASPI_SW_REG")
      (value "OKI-78SR-5_1.5-W36-C")
      (footprint "eagle-import:OKI-78SR")
      (fields
        (field (name "ARROW_PART_NUMBER") "OKI-78SR-5/1.5-W36-C")
        (field (name "RS_PART_NUMBER") "1736928")
      )
      (libsource (lib "eagle-import") (part "OKI-78SR-5_1.5-W36-C"))
    )
  )
  (nets
    (net (code "1") (name "CMP_INT") (class "Default")
      (node (ref "COMPASS_HEADER") (pin "4") (pinfunction "4_4") (pintype "passive"))
      (node (ref "IC5") (pin "40") (pinfunction "PE9_40") (pintype "bidirectional"))
    )
    (net (code "2") (name "CMP_MISO") (class "Default")
      (node (ref "IC5") (pin "53") (pinfunction "PB14_53") (pintype "bidirectional"))
      (node (ref "SPI_CMP") (pin "6") (pinfunction "MISO_6") (pintype "bidirectional"))
    )
    (net (code "3") (name "CMP_MOSI") (class "Default")
      (node (ref "IC5") (pin "54") (pinfunction "PB15_54") (pintype "bidirectional"))
      (node (ref "SPI_CMP") (pin "5") (pinfunction "SDA/MOSI_5") (pintype "bidirectional"))
    )
    (net (code "4") (name "CMP_SCL") (class "Default")
      (node (ref "COMPASS_HEADER") (pin "6") (pinfunction "6_6") (pintype "passive"))
      (node (ref "IC5") (pin "95") (pinfunction "PB8_95") (pintype "bidirectional"))
      (node (ref "R47") (pin "1") (pinfunction "1_1") (pintype "passive"))
    )
    (net (code "5") (name "CMP_SCLK") (class "Default")
      (node (ref "IC5") (pin "52") (pinfunction "PB13_52") (pintype "bidirectional"))
      (node (ref "SPI_CMP") (pin "3") (pinfunction "SCL/SCLK_3") (pintype "bidirectional"))
    )
    (net (code "6") (name "CMP_SDA") (class "Default")
      (node (ref "COMPASS_HEADER") (pin "8") (pinfunction "8_8") (pintype "passive"))
      (node (ref "IC5") (pin "96") (pinfunction "PB9_96") (pintype "bidirectional"))
      (node (ref "R49") (pin "1") (pinfunction "1_1") (pintype "passive"))
    )
    (net (code "7") (name "CMP_SPI_INT") (class "Default")
      (node (ref "IC5") (pin "38") (pinfunction "PE7_38") (pintype "bidirectional"))
      (node (ref "SPI_CMP") (pin "1") (pinfunction "INT_1") (pintype "bidirectional"))
    )
    (net (code "8") (name "CMP_TRG") (class "Default")
      (node (ref "COMPASS_HEADER") (pin "10") (pinfunction "10_10") (pintype "passive"))
      (node (ref "IC5") (pin "41") (pinfunction "PE10_41") (pintype "bidirectional"))
    )
    (net (code "9") (name "CMP_TRIG") (class "Default")
      (node (ref "IC5") (pin "39") (pinfunction "PE8_39") (pintype "bidirectional"))
      (node (ref "SPI_CMP") (pin "7") (pinfunction "INT/TRIG_7") (pintype "bidirectional"))
    )
    (net (code "10") (name "C_MOS") (class "Default")
      (node (ref "CON_SW") (pin "G") (pinfunction "G_G") (pintype "passive"))
      (node (ref "IC5") (pin "69") (pinfunction "PA10_69") (pintype "bidirectional"))
      (node (ref "R15") (pin "2") (pinfunction "2_2") (pintype "passive"))
    )
    (net (code "11") (name "ESP_GPIO0") (class "Default")
      (node (ref "ESP8266_HEADER") (pin "5") (pinfunction "5_5") (pintype "passive"))
      (node (ref "ESP_DEBUG") (pin "8") (pinfunction "8_8") (pintype "passive"))
      (node (ref "JP2") (pin "3") (pinfunction "3_3") (pintype "passive"))
    )
    (net (code "12") (name "ESP_GPIO2") (class "Default")
      (node (ref "BOOT0") (pin "G") (pinfunction "G_G") (pintype "passive"))
      (node (ref "ESP8266_HEADER") (pin "3") (pinfunction "3_3") (pintype "passive"))
      (node (ref "ESP_DEBUG") (pin "7") (pinfunction "7_7") (pintype "passive"))
      (node (ref "R50") (pin "2") (pinfunction "2_2") (pintype "passive"))
    )
    (net (code "13") (name "ESP_RX") (class "Default")
      (node (ref "ESP8266_HEADER") (pin "7") (pinfunction "7_7") (pintype "passive"))
      (node (ref "ESP_DEBUG") (pin "4") (pinfunction "4_4") (pintype "passive"))
      (node (ref "IC5") (pin "47") (pinfunction "PB10_47") (pintype "bidirectional"))
    )
    (net (code "14") (name "ESP_TX") (class "Default")
      (node (ref "ESP8266_HEADER") (pin "2") (pinfunction "2_2") (pintype "passive"))
      (node (ref "ESP_DEBUG") (pin "5") (pinfunction "5_5") (pintype "passive"))
      (node (ref "IC5") (pin "48") (pinfunction "PB11_48") (pintype "bidirectional"))
    )
    (net (code "15") (name "GND") (class "Default")
      (node (ref "C1") (pin "-") (pinfunction "-_-") (pintype "passive"))
      (node (ref "C10") (pin "2") (pinfunction "2_2") (pintype "passive"))
      (node (ref "C13") (pin "1") (pinfunction "1_1") (pintype "passive"))
      (node (ref "C14") (pin "2") (pinfunction "2_2") (pintype "passive"))
      (node (ref "C15") (pin "2") (pinfunction "2_2") (pintype "passive"))
      (node (ref "C16") (pin "2") (pinfunction "2_2") (pintype "passive"))
      (node (ref "C17") (pin "2") (pinfunction "2_2") (pintype "passive"))
      (node (ref "C18") (pin "2") (pinfunction "2_2") (pintype "passive"))
      (node (ref "C19") (pin "2") (pinfunction "2_2") (pintype "passive"))
      (node (ref "C2") (pin "-") (pinfunction "-_-") (pintype "passive"))
      (node (ref "C20") (pin "2") (pinfunction "2_2") (pintype "passive"))
      (node (ref "C25") (pin "2") (pinfunction "2_2") (pintype "passive"))
      (node (ref "C26") (pin "2") (pinfunction "2_2") (pintype "passive"))
      (node (ref "C3") (pin "-") (pinfunction "-_-") (pintype "passive"))
      (node (ref "C30") (pin "2") (pinfunction "2_2") (pintype "passive"))
      (node (ref "C31") (pin "2") (pinfunction "2_2") (pintype "passive"))
      (node (ref "C32") (pin "1") (pinfunction "1_1") (pintype "passive"))
      (node (ref "C33") (pin "1") (pinfunction "1_1") (pintype "passive"))
      (node (ref "C34") (pin "2") (pinfunction "2_2") (pintype "passive"))
      (node (ref "C35") (pin "2") (pinfunction "2_2") (pintype "passive"))
      (node (ref "C38") (pin "1") (pinfunction "1_1") (pintype "passive"))
      (node (ref "C39") (pin "2") (pinfunction "2_2") (pintype "passive"))
      (node (ref "C4") (pin "-") (pinfunction "-_-") (pintype "passive"))
      (node (ref "C40") (pin "2") (pinfunction "2_2") (pintype "passive"))
      (node (ref "C41") (pin "2") (pinfunction "2_2") (pintype "passive"))
      (node (ref "C42") (pin "2") (pinfunction "2_2") (pintype "passive"))
      (node (ref "C43") (pin "2") (pinfunction "2_2") (pintype "passive"))
      (node (ref "C44") (pin "2") (pinfunction "2_2") (pintype "passive"))
      (node (ref "C45") (pin "2") (pinfunction "2_2") (pintype "passive"))
      (node (ref "C5") (pin "2") (pinfunction "2_2") (pintype "passive"))
      (node (ref "C6") (pin "2") (pinfunction "2_2") (pintype "passive"))
      (node (ref "C7") (pin "2") (pinfunction "2_2") (pintype "passive"))
      (node (ref "C8") (pin "2") (pinfunction "2_2") (pintype "passive"))
      (node (ref "C9") (pin "2") (pinfunction "2_2") (pintype "passive"))
      (node (ref "COMPASS_HEADER") (pin "3") (pinfunction "3_3") (pintype "passive"))
      (node (ref "COMPASS_HEADER") (pin "5") (pinfunction "5_5") (pintype "passive"))
      (node (ref "COMPASS_HEADER") (pin "7") (pinfunction "7_7") (pintype "passive"))
      (node (ref "COMPASS_HEADER") (pin "9") (pinfunction "9_9") (pintype "passive"))
      (node (ref "CONVPOW") (pin "1") (pinfunction "GND_1") (pintype "power_in"))
      (node (ref "CON_SW") (pin "S") (pinfunction "S_S") (pintype "passive"))
      (node (ref "DCIN") (pin "1") (pinfunction "GND_1") (pintype "power_in"))
      (node (ref "DCOUT") (pin "1") (pinfunction "GND_1") (pintype "power_in"))
      (node (ref "ESP8266_HEADER") (pin "1") (pinfunction "1_1") (pintype "passive"))
      (node (ref "ESP_DEBUG") (pin "1") (pinfunction "1_1") (pintype "passive"))
      (node (ref "GPS_DEBUG") (pin "1") (pinfunction "1_1") (pintype "passive"))
      (node (ref "GPS_HEADER") (pin "4") (pinfunction "4_4") (pintype "passive"))
      (node (ref "IC5") (pin "10") (pinfunction "VSS_10") (pintype "passive"))
      (node (ref "IC5") (pin "20") (pinfunction "VSSA_20") (pintype "passive"))
      (node (ref "IC5") (pin "27") (pinfunction "VSS_27") (pintype "passive"))
      (node (ref "IC5") (pin "74") (pinfunction "VSS_74") (pintype "passive"))
      (node (ref "IC5") (pin "99") (pinfunction "VSS_99") (pintype "passive"))
      (node (ref "LASR_SW") (pin "S") (pinfunction "S_S") (pintype "passive"))
      (node (ref "LDR_SW") (pin "S") (pinfunction "S_S") (pintype "passive"))
      (node (ref "LED1") (pin "C") (pinfunction "C_C") (pintype "passive"))
      (node (ref "LEFT_MOTOR") (pin "3") (pinfunction "3_3") (pintype "bidirectional"))
      (node (ref "LEFT_MOTOR") (pin "5") (pinfunction "5_5") (pintype "bidirectional"))
      (node (ref "LM_SW") (pin "S") (pinfunction "S_S") (pintype "passive"))
      (node (ref "LTE_PWR") (pin "4") (pinfunction "4_4") (pintype "bidirectional"))
      (node (ref "LTE_SW_REG") (pin "2") (pinfunction "COMMON(GROUND)_2") (pintype "bidirectional"))
      (node (ref "MICRO_REG") (pin "1") (pinfunction "ADJ/GND_1") (pintype "power_in"))
      (node (ref "MICRO_SW_REG") (pin "2") (pinfunction "COMMON(GROUND)_2") (pintype "bidirectional"))
      (node (ref "MOTOR_L_SENSE_IN") (pin "P$4") (pinfunction "1_P$4") (pintype "passive"))
      (node (ref "MOTOR_L_SENSE_OUT") (pin "P$4") (pinfunction "1_P$4") (pintype "passive"))
      (node (ref "MOTOR_R_SENSE_IN") (pin "P$4") (pinfunction "1_P$4") (pintype "passive"))
      (node (ref "MOTOR_R_SENSE_OUT") (pin "P$4") (pinfunction "1_P$4") (pintype "passive"))
      (node (ref "NRST") (pin "S") (pinfunction "S_S") (pintype "passive"))
      (node (ref "PCBPOWER") (pin "1") (pinfunction "GND_1") (pintype "power_in"))
      (node (ref "PCB_SENSE_IN") (pin "P$4") (pinfunction "1_P$4") (pintype "passive"))
      (node (ref "PCB_SENSE_OUT") (pin "P$4") (pinfunction "1_P$4") (pintype "passive"))
      (node (ref "PWR") (pin "C") (pinfunction "C_C") (pintype "passive"))
      (node (ref "R13") (pin "1") (pinfunction "1_1") (pintype "passive"))
      (node (ref "R15") (pin "1") (pinfunction "1_1") (pintype "passive"))
      (node (ref "R18") (pin "2") (pinfunction "2_2") (pintype "passive"))
      (node (ref "R2") (pin "2") (pinfunction "2_2") (pintype "passive"))
      (node (ref "R20") (pin "2") (pinfunction "2_2") (pintype "passive"))
      (node (ref "R22") (pin "2") (pinfunction "2_2") (pintype "passive"))
      (node (ref "R24") (pin "2") (pinfunction "2_2") (pintype "passive"))
      (node (ref "R26") (pin "2") (pinfunction "2_2") (pintype "passive"))
      (node (ref "R28") (pin "2") (pinfunction "2_2") (pintype "passive"))
      (node (ref "R30") (pin "2") (pinfunction "2_2") (pintype "passive"))
      (node (ref "R32") (pin "2") (pinfunction "2_2") (pintype "passive"))
      (node (ref "R34") (pin "2") (pinfunction "2_2") (pintype "passive"))
      (node (ref "R35") (pin "1") (pinfunction "1_1") (pintype "passive"))
      (node (ref "R4") (pin "2") (pinfunction "2_2") (pintype "passive"))
      (node (ref "R46") (pin "1") (pinfunction "1_1") (pintype "passive"))
      (node (ref "R50") (pin "1") (pinfunction "1_1") (pintype "passive"))
      (node (ref "R51") (pin "2") (pinfunction "2_2") (pintype "passive"))
      (node (ref "R53") (pin "1") (pinfunction "1_1") (pintype "passive"))
      (node (ref "R6") (pin "2") (pinfunction "2_2") (pintype "passive"))
      (node (ref "R8") (pin "2") (pinfunction "2_2") (pintype "passive"))
      (node (ref "RASPI_PWR") (pin "4") (pinfunction "4_4") (pintype "bidirectional"))
      (node (ref "RASPI_SW") (pin "S") (pinfunction "S_S") (pintype "passive"))
      (node (ref "RIGHT_MOTOR") (pin "3") (pinfunction "3_3") (pintype "bidirectional"))
      (node (ref "RIGHT_MOTOR") (pin "5") (pinfunction "5_5") (pintype "bidirectional"))
      (node (ref "RM_SW") (pin "S") (pinfunction "S_S") (pintype "passive"))
      (node (ref "SOLAR") (pin "1") (pinfunction "GND_1") (pintype "power_in"))
      (node (ref "SPI_CMP") (pin "10") (pinfunction "N/C_3_10") (pintype "bidirectional"))
      (node (ref "SPI_CMP") (pin "11") (pinfunction "A1_11") (pintype "bidirectional"))
      (node (ref "SPI_CMP") (pin "12") (pinfunction "A0_12") (pintype "bidirectional"))
      (node (ref "SPI_CMP") (pin "13") (pinfunction "VSS_13") (pintype "bidirectional"))
      (node (ref "SPI_CMP") (pin "14") (pinfunction "N/C_4_14") (pintype "bidirectional"))
      (node (ref "SPI_CMP") (pin "16") (pinfunction "N/C_5_16") (pintype "bidirectional"))
      (node (ref "SPI_CMP") (pin "2") (pinfunction "SENB/CS_2") (pintype "bidirectional"))
      (node (ref "SPI_CMP") (pin "4") (pinfunction "N/C_1_4") (pintype "bidirectional"))
      (node (ref "SPI_CMP") (pin "9") (pinfunction "N/C_2_9") (pintype "bidirectional"))
      (node (ref "STLINK") (pin "3") (pinfunction "3_3") (pintype "passive"))
    )
    (net (code "16") (name "GND_BREAKOUT") (class "Default")
      (node (ref "C11") (pin "2") (pinfunction "2_2") (pintype "passive"))
      (node (ref "C12") (pin "2") (pinfunction "2_2") (pintype "passive"))
      (node (ref "C21") (pin "1") (pinfunction "1_1") (pintype "passive"))
      (node (ref "C22") (pin "1") (pinfunction "1_1") (pintype "passive"))
      (node (ref "CMP_BRKOUT") (pin "3") (pinfunction "3_3") (pintype "passive"))
      (node (ref "CMP_BRKOUT") (pin "5") (pinfunction "5_5") (pintype "passive"))
      (node (ref "CMP_BRKOUT") (pin "7") (pinfunction "7_7") (pintype "passive"))
      (node (ref "CMP_BRKOUT") (pin "9") (pinfunction "9_9") (pintype "passive"))
      (node (ref "IC3") (pin "10") (pinfunction "N/C_3_10") (pintype "bidirectional"))
      (node (ref "IC3") (pin "13") (pinfunction "VSS_13") (pintype "bidirectional"))
      (node (ref "IC3") (pin "14") (pinfunction "N/C_4_14") (pintype "bidirectional"))
      (node (ref "IC3") (pin "16") (pinfunction "N/C_5_16") (pintype "bidirectional"))
      (node (ref "IC3") (pin "4") (pinfunction "N/C_1_4") (pintype "bidirectional"))
      (node (ref "IC3") (pin "9") (pinfunction "N/C_2_9") (pintype "bidirectional"))
    )
    (net (code "17") (name "GPS_RX") (class "Default")
      (node (ref "GPS_DEBUG") (pin "4") (pinfunction "4_4") (pintype "passive"))
      (node (ref "GPS_HEADER") (pin "2") (pinfunction "2_2") (pintype "passive"))
      (node (ref "IC5") (pin "92") (pinfunction "PB6_92") (pintype "bidirectional"))
    )
    (net (code "18") (name "GPS_TX") (class "Default")
      (node (ref "GPS_DEBUG") (pin "5") (pinfunction "5_5") (pintype "passive"))
      (node (ref "GPS_HEADER") (pin "3") (pinfunction "3_3") (pintype "passive"))
      (node (ref "IC5") (pin "93") (pinfunction "PB7_93") (pintype "bidirectional"))
    )
    (net (code "19") (name "LASER_MOS") (class "Default")
      (node (ref "IC5") (pin "71") (pinfunction "PA12_71") (pintype "bidirectional"))
      (node (ref "LASR_SW") (pin "G") (pinfunction "G_G") (pintype "passive"))
      (node (ref "R55") (pin "1") (pinfunction "1_1") (pintype "passive"))
    )
    (net (code "20") (name "LDR0") (class "Default")
      (node (ref "IC5") (pin "23") (pinfunction "PA0_23") (pintype "bidirectional"))
      (node (ref "LDR0") (pin "TP") (pinfunction "TP_TP") (pintype "input"))
      (node (ref "LDR_HEADER") (pin "2") (pinfunction "2_2") (pintype "passive"))
      (node (ref "R37") (pin "1") (pinfunction "1_1") (pintype "passive"))
    )
    (net (code "21") (name "LDR1") (class "Default")
      (node (ref "IC5") (pin "24") (pinfunction "PA1_24") (pintype "bidirectional"))
      (node (ref "LDR1") (pin "TP") (pinfunction "TP_TP") (pintype "input"))
      (node (ref "LDR_HEADER") (pin "4") (pinfunction "4_4") (pintype "passive"))
      (node (ref "R39") (pin "1") (pinfunction "1_1") (pintype "passive"))
    )
    (net (code "22") (name "LDR2") (class "Default")
      (node (ref "IC5") (pin "25") (pinfunction "PA2_25") (pintype "bidirectional"))
      (node (ref "LDR2") (pin "TP") (pinfunction "TP_TP") (pintype "input"))
      (node (ref "LDR_HEADER") (pin "6") (pinfunction "6_6") (pintype "passive"))
      (node (ref "R40") (pin "1") (pinfunction "1_1") (pintype "passive"))
    )
    (net (code "23") (name "LDR3") (class "Default")
      (node (ref "IC5") (pin "26") (pinfunction "PA3_26") (pintype "bidirectional"))
      (node (ref "LDR3") (pin "TP") (pinfunction "TP_TP") (pintype "input"))
      (node (ref "LDR_HEADER") (pin "8") (pinfunction "8_8") (pintype "passive"))
      (node (ref "R41") (pin "1") (pinfunction "1_1") (pintype "passive"))
    )
    (net (code "24") (name "LDR4") (class "Default")
      (node (ref "IC5") (pin "29") (pinfunction "PA4_29") (pintype "bidirectional"))
      (node (ref "LDR4") (pin "TP") (pinfunction "TP_TP") (pintype "input"))
      (node (ref "LDR_HEADER") (pin "10") (pinfunction "10_10") (pintype "passive"))
      (node (ref "R42") (pin "1") (pinfunction "1_1") (pintype "passive"))
    )
    (net (code "25") (name "LDR_MOS") (class "Default")
      (node (ref "IC5") (pin "77") (pinfunction "PA15_77") (pintype "bidirectional"))
      (node (ref "LDR_SW") (pin "G") (pinfunction "G_G") (pintype "passive"))
      (node (ref "R54") (pin "1") (pinfunction "1_1") (pintype "passive"))
    )
    (net (code "26") (name "L_MOS") (class "Default")
      (node (ref "IC5") (pin "67") (pinfunction "PA8_67") (pintype "bidirectional"))
      (node (ref "LM_SW") (pin "G") (pinfunction "G_G") (pintype "passive"))
      (node (ref "R46") (pin "2") (pinfunction "2_2") (pintype "passive"))
    )
    (net (code "27") (name "L_PWM") (class "Default")
      (node (ref "IC5") (pin "63") (pinfunction "PC6_63") (pintype "bidirectional"))
      (node (ref "LEFT_MOTOR") (pin "1") (pinfunction "1_1") (pintype "bidirectional"))
    )
    (net (code "28") (name "MOTOR_L_CELL1") (class "Default")
      (node (ref "C16") (pin "1") (pinfunction "1_1") (pintype "passive"))
      (node (ref "IC5") (pin "35") (pinfunction "PB0_35") (pintype "bidirectional"))
      (node (ref "L_CELL1") (pin "TP") (pinfunction "TP_TP") (pintype "input"))
      (node (ref "R27") (pin "2") (pinfunction "2_2") (pintype "passive"))
      (node (ref "R28") (pin "1") (pinfunction "1_1") (pintype "passive"))
    )
    (net (code "29") (name "MOTOR_L_CELL2") (class "Default")
      (node (ref "C15") (pin "1") (pinfunction "1_1") (pintype "passive"))
      (node (ref "IC5") (pin "36") (pinfunction "PB1_36") (pintype "bidirectional"))
      (node (ref "L_CELL2") (pin "TP") (pinfunction "TP_TP") (pintype "input"))
      (node (ref "R25") (pin "2") (pinfunction "2_2") (pintype "passive"))
      (node (ref "R26") (pin "1") (pinfunction "1_1") (pintype "passive"))
    )
    (net (code "30") (name "MOTOR_L_CELL3") (class "Default")
      (node (ref "C9") (pin "1") (pinfunction "1_1") (pintype "passive"))
      (node (ref "IC5") (pin "15") (pinfunction "PC0_15") (pintype "bidirectional"))
      (node (ref "L_CELL3") (pin "TP") (pinfunction "TP_TP") (pintype "input"))
      (node (ref "R23") (pin "2") (pinfunction "2_2") (pintype "passive"))
      (node (ref "R24") (pin "1") (pinfunction "1_1") (pintype "passive"))
    )
    (net (code "31") (name "MOTOR_R_CELL1") (class "Default")
      (node (ref "C20") (pin "1") (pinfunction "1_1") (pintype "passive"))
      (node (ref "IC5") (pin "16") (pinfunction "PC1_16") (pintype "bidirectional"))
      (node (ref "R33") (pin "2") (pinfunction "2_2") (pintype "passive"))
      (node (ref "R34") (pin "1") (pinfunction "1_1") (pintype "passive"))
      (node (ref "R_CELL1") (pin "TP") (pinfunction "TP_TP") (pintype "input"))
    )
    (net (code "32") (name "MOTOR_R_CELL2") (class "Default")
      (node (ref "C19") (pin "1") (pinfunction "1_1") (pintype "passive"))
      (node (ref "IC5") (pin "17") (pinfunction "PC2_17") (pintype "bidirectional"))
      (node (ref "R31") (pin "2") (pinfunction "2_2") (pintype "passive"))
      (node (ref "R32") (pin "1") (pinfunction "1_1") (pintype "passive"))
      (node (ref "R_CELL2") (pin "TP") (pinfunction "TP_TP") (pintype "input"))
    )
    (net (code "33") (name "MOTOR_R_CELL3") (class "Default")
      (node (ref "C17") (pin "1") (pinfunction "1_1") (pintype "passive"))
      (node (ref "IC5") (pin "18") (pinfunction "PC3_18") (pintype "bidirectional"))
      (node (ref "R29") (pin "2") (pinfunction "2_2") (pintype "passive"))
      (node (ref "R30") (pin "1") (pinfunction "1_1") (pintype "passive"))
      (node (ref "R_CELL3") (pin "TP") (pinfunction "TP_TP") (pintype "input"))
    )
    (net (code "34") (name "NRST") (class "Default")
      (node (ref "NRST") (pin "D") (pinfunction "D_D") (pintype "passive"))
      (node (ref "RST") (pin "C") (pinfunction "C_C") (pintype "passive"))
      (node (ref "STLINK") (pin "5") (pinfunction "5_5") (pintype "passive"))
    )
    (net (code "35") (name "Net-(BOOT0-PadD)") (class "Default")
      (node (ref "BOOT0") (pin "D") (pinfunction "D_D") (pintype "passive"))
      (node (ref "JP1") (pin "3") (pinfunction "3_3") (pintype "passive"))
      (node (ref "R36") (pin "1") (pinfunction "1_1") (pintype "passive"))
    )
    (net (code "36") (name "Net-(BOOT0-PadS)") (class "Default")
      (node (ref "BOOT0") (pin "S") (pinfunction "S_S") (pintype "passive"))
      (node (ref "R51") (pin "1") (pinfunction "1_1") (pintype "passive"))
    )
    (net (code "37") (name "Net-(C39-Pad1)") (class "Default")
      (node (ref "C39") (pin "1") (pinfunction "1_1") (pintype "passive"))
      (node (ref "Q11") (pin "2") (pinfunction "2_2") (pintype "passive"))
      (node (ref "R38") (pin "2") (pinfunction "2_2") (pintype "passive"))
    )
    (net (code "38") (name "Net-(CONVPOW-POS)") (class "Default")
      (node (ref "CONVPOW") (pin "2") (pinfunction "POS_2") (pintype "power_in"))
      (node (ref "CONV_SW_REG") (pin "3") (pinfunction "POSITIVE_OUTPUT_3") (pintype "bidirectional"))
    )
    (net (code "39") (name "Net-(CONV_SW_REG-COMMON(GROUND))") (class "Default")
      (node (ref "CONV_SW_REG") (pin "2") (pinfunction "COMMON(GROUND)_2") (pintype "bidirectional"))
      (node (ref "CON_SW") (pin "D") (pinfunction "D_D") (pintype "passive"))
      (node (ref "R43") (pin "2") (pinfunction "2_2") (pintype "passive"))
    )
    (net (code "40") (name "Net-(D1-ANODE_1)") (class "Default")
      (node (ref "D1") (pin "1") (pinfunction "ANODE_1_1") (pintype "bidirectional"))
      (node (ref "D1") (pin "2") (pinfunction "ANODE_2_2") (pintype "bidirectional"))
      (node (ref "DCIN") (pin "2") (pinfunction "POS_2") (pintype "power_in"))
    )
    (net (code "41") (name "Net-(D1-CATHODE_(HEATSINK))") (class "Default")
      (node (ref "D1") (pin "3") (pinfunction "CATHODE_(HEATSINK)_3") (pintype "bidirectional"))
      (node (ref "D3") (pin "3") (pinfunction "CATHODE_(HEATSINK)_3") (pintype "bidirectional"))
      (node (ref "DCOUT") (pin "2") (pinfunction "POS_2") (pintype "power_in"))
    )
    (net (code "42") (name "Net-(D3-ANODE_1)") (class "Default")
      (node (ref "D3") (pin "1") (pinfunction "ANODE_1_1") (pintype "bidirectional"))
      (node (ref "D3") (pin "2") (pinfunction "ANODE_2_2") (pintype "bidirectional"))
      (node (ref "SOLAR") (pin "2") (pinfunction "POS_2") (pintype "power_in"))
    )
    (net (code "43") (name "Net-(ESP8266_HEADER-Pad4)") (class "Default")
      (node (ref "ESP8266_HEADER") (pin "4") (pinfunction "4_4") (pintype "passive"))
      (node (ref "ESP8266_HEADER") (pin "8") (pinfunction "8_8") (pintype "passive"))
      (node (ref "JP4") (pin "2") (pinfunction "2_2") (pintype "passive"))
    )
    (net (code "44") (name "Net-(ESP_DEBUG-Pad3)") (class "Default")
      (node (ref "ESP_DEBUG") (pin "3") (pinfunction "3_3") (pintype "passive"))
      (node (ref "JP4") (pin "3") (pinfunction "3_3") (pintype "passive"))
    )
    (net (code "45") (name "Net-(GPS_DEBUG-Pad3)") (class "Default")
      (node (ref "GPS_DEBUG") (pin "3") (pinfunction "3_3") (pintype "passive"))
      (node (ref "JP5") (pin "1") (pinfunction "1_1") (pintype "passive"))
    )
    (net (code "46") (name "Net-(GPS_HEADER-Pad1)") (class "Default")
      (node (ref "GPS_HEADER") (pin "1") (pinfunction "1_1") (pintype "passive"))
      (node (ref "JP5") (pin "3") (pinfunction "3_3") (pintype "passive"))
    )
    (net (code "47") (name "Net-(IC3-INT)") (class "Default")
      (node (ref "CMP_BRKOUT") (pin "4") (pinfunction "4_4") (pintype "passive"))
      (node (ref "IC3") (pin "1") (pinfunction "INT_1") (pintype "bidirectional"))
    )
    (net (code "48") (name "Net-(IC3-INT{slash}TRIG)") (class "Default")
      (node (ref "CMP_BRKOUT") (pin "10") (pinfunction "10_10") (pintype "passive"))
      (node (ref "IC3") (pin "7") (pinfunction "INT/TRIG_7") (pintype "bidirectional"))
    )
    (net (code "49") (name "Net-(IC3-SCL{slash}SCLK)") (class "Default")
      (node (ref "C22") (pin "2") (pinfunction "2_2") (pintype "passive"))
      (node (ref "CMP_BRKOUT") (pin "6") (pinfunction "6_6") (pintype "passive"))
      (node (ref "IC3") (pin "3") (pinfunction "SCL/SCLK_3") (pintype "bidirectional"))
      (node (ref "R10") (pin "2") (pinfunction "2_2") (pintype "passive"))
    )
    (net (code "50") (name "Net-(IC3-SDA{slash}MOSI)") (class "Default")
      (node (ref "C21") (pin "2") (pinfunction "2_2") (pintype "passive"))
      (node (ref "CMP_BRKOUT") (pin "8") (pinfunction "8_8") (pintype "passive"))
      (node (ref "IC3") (pin "5") (pinfunction "SDA/MOSI_5") (pintype "bidirectional"))
      (node (ref "R9") (pin "2") (pinfunction "2_2") (pintype "passive"))
    )
    (net (code "51") (name "Net-(IC5-BOOT0)") (class "Default")
      (node (ref "IC5") (pin "94") (pinfunction "BOOT0_94") (pintype "input"))
      (node (ref "JP1") (pin "2") (pinfunction "2_2") (pintype "passive"))
    )
    (net (code "52") (name "Net-(IC5-NRST)") (class "Default")
      (node (ref "C5") (pin "1") (pinfunction "1_1") (pintype "passive"))
      (node (ref "IC5") (pin "14") (pinfunction "NRST_14") (pintype "bidirectional"))
      (node (ref "R12") (pin "2") (pinfunction "2_2") (pintype "passive"))
      (node (ref "R56") (pin "2") (pinfunction "2_2") (pintype "passive"))
    )
    (net (code "53") (name "Net-(IC5-PB2)") (class "Default")
      (node (ref "IC5") (pin "37") (pinfunction "PB2_37") (pintype "bidirectional"))
      (node (ref "JP3") (pin "2") (pinfunction "2_2") (pintype "passive"))
    )
    (net (code "54") (name "Net-(IC5-PD15)") (class "Default")
      (node (ref "IC5") (pin "62") (pinfunction "PD15_62") (pintype "bidirectional"))
      (node (ref "R45") (pin "1") (pinfunction "1_1") (pintype "passive"))
    )
    (net (code "55") (name "Net-(IC5-PH0)") (class "Default")
      (node (ref "C40") (pin "1") (pinfunction "1_1") (pintype "passive"))
      (node (ref "IC5") (pin "12") (pinfunction "PH0_12") (pintype "bidirectional"))
      (node (ref "Q11") (pin "1") (pinfunction "1_1") (pintype "passive"))
    )
    (net (code "56") (name "Net-(IC5-PH1)") (class "Default")
      (node (ref "IC5") (pin "13") (pinfunction "PH1_13") (pintype "bidirectional"))
      (node (ref "R38") (pin "1") (pinfunction "1_1") (pintype "passive"))
    )
    (net (code "57") (name "Net-(IC5-VCAP_1)") (class "Default")
      (node (ref "C33") (pin "2") (pinfunction "2_2") (pintype "passive"))
      (node (ref "IC5") (pin "49") (pinfunction "VCAP_1_49") (pintype "power_in"))
    )
    (net (code "58") (name "Net-(IC5-VCAP_2)") (class "Default")
      (node (ref "C32") (pin "2") (pinfunction "2_2") (pintype "passive"))
      (node (ref "IC5") (pin "73") (pinfunction "VCAP_2_73") (pintype "power_in"))
    )
    (net (code "59") (name "Net-(IC5-VDDA)") (class "Default")
      (node (ref "C31") (pin "1") (pinfunction "1_1") (pintype "passive"))
      (node (ref "C34") (pin "1") (pinfunction "1_1") (pintype "passive"))
      (node (ref "IC5") (pin "22") (pinfunction "VDDA_22") (pintype "power_in"))
      (node (ref "L1") (pin "1") (pinfunction "1_1") (pintype "passive"))
      (node (ref "R11") (pin "2") (pinfunction "2_2") (pintype "passive"))
    )
    (net (code "60") (name "Net-(IC5-VREF+)") (class "Default")
      (node (ref "C30") (pin "1") (pinfunction "1_1") (pintype "passive"))
      (node (ref "C35") (pin "1") (pinfunction "1_1") (pintype "passive"))
      (node (ref "IC5") (pin "21") (pinfunction "VREF+_21") (pintype "power_in"))
      (node (ref "R11") (pin "1") (pinfunction "1_1") (pintype "passive"))
    )
    (net (code "61") (name "Net-(JP1-Pad1)") (class "Default")
      (node (ref "JP1") (pin "1") (pinfunction "1_1") (pintype "passive"))
      (node (ref "R35") (pin "2") (pinfunction "2_2") (pintype "passive"))
    )
    (net (code "62") (name "Net-(JP2-Pad2)") (class "Default")
      (node (ref "JP2") (pin "2") (pinfunction "2_2") (pintype "passive"))
      (node (ref "NRST") (pin "G") (pinfunction "G_G") (pintype "passive"))
      (node (ref "R52") (pin "2") (pinfunction "2_2") (pintype "passive"))
    )
    (net (code "63") (name "Net-(JP3-Pad1)") (class "Default")
      (node (ref "JP3") (pin "1") (pinfunction "1_1") (pintype "passive"))
      (node (ref "R14") (pin "2") (pinfunction "2_2") (pintype "passive"))
    )
    (net (code "64") (name "Net-(JP3-Pad3)") (class "Default")
      (node (ref "JP3") (pin "3") (pinfunction "3_3") (pintype "passive"))
      (node (ref "R13") (pin "2") (pinfunction "2_2") (pintype "passive"))
    )
    (net (code "65") (name "Net-(LASER_HEADER-Pad1)") (class "Default")
      (node (ref "LASER_HEADER") (pin "1") (pinfunction "1_1") (pintype "passive"))
      (node (ref "LASER_HEADER") (pin "3") (pinfunction "3_3") (pintype "passive"))
      (node (ref "LASER_HEADER") (pin "5") (pinfunction "5_5") (pintype "passive"))
      (node (ref "LASER_HEADER") (pin "7") (pinfunction "7_7") (pintype "passive"))
      (node (ref "LASER_HEADER") (pin "9") (pinfunction "9_9") (pintype "passive"))
      (node (ref "LASR_SW") (pin "D") (pinfunction "D_D") (pintype "passive"))
    )
    (net (code "66") (name "Net-(LDR_SW-PadD)") (class "Default")
      (node (ref "LDR_SW") (pin "D") (pinfunction "D_D") (pintype "passive"))
      (node (ref "R37") (pin "2") (pinfunction "2_2") (pintype "passive"))
      (node (ref "R39") (pin "2") (pinfunction "2_2") (pintype "passive"))
      (node (ref "R40") (pin "2") (pinfunction "2_2") (pintype "passive"))
      (node (ref "R41") (pin "2") (pinfunction "2_2") (pintype "passive"))
      (node (ref "R42") (pin "2") (pinfunction "2_2") (pintype "passive"))
    )
    (net (code "67") (name "Net-(LED1-PadA)") (class "Default")
      (node (ref "LED1") (pin "A") (pinfunction "A_A") (pintype "passive"))
      (node (ref "R45") (pin "2") (pinfunction "2_2") (pintype "passive"))
    )
    (net (code "68") (name "Net-(LEFT_MOTOR-Pad4)") (class "Default")
      (node (ref "LEFT_MOTOR") (pin "4") (pinfunction "4_4") (pintype "bidirectional"))
      (node (ref "LM_SW") (pin "D") (pinfunction "D_D") (pintype "passive"))
    )
    (net (code "69") (name "Net-(LTE_PWR-Pad2)") (class "Default")
      (node (ref "LTE_PWR") (pin "2") (pinfunction "2_2") (pintype "bidirectional"))
      (node (ref "R7") (pin "2") (pinfunction "2_2") (pintype "passive"))
      (node (ref "R8") (pin "1") (pinfunction "1_1") (pintype "passive"))
    )
    (net (code "70") (name "Net-(LTE_PWR-Pad3)") (class "Default")
      (node (ref "LTE_PWR") (pin "3") (pinfunction "3_3") (pintype "bidirectional"))
      (node (ref "R1") (pin "2") (pinfunction "2_2") (pintype "passive"))
      (node (ref "R2") (pin "1") (pinfunction "1_1") (pintype "passive"))
    )
    (net (code "71") (name "Net-(LTE_SW_REG-POSITIVE_OUTPUT)") (class "Default")
      (node (ref "C1") (pin "+") (pinfunction "+_+") (pintype "passive"))
      (node (ref "LTE_PWR") (pin "1") (pinfunction "1_1") (pintype "bidirectional"))
      (node (ref "LTE_SW_REG") (pin "3") (pinfunction "POSITIVE_OUTPUT_3") (pintype "bidirectional"))
      (node (ref "R1") (pin "1") (pinfunction "1_1") (pintype "passive"))
      (node (ref "R7") (pin "1") (pinfunction "1_1") (pintype "passive"))
    )
    (net (code "72") (name "Net-(MOTOR_L_SENSE_INA-1)") (class "Default")
      (node (ref "MOTOR_L_SENSE_IN") (pin "P$1") (pinfunction "1_P$1") (pintype "passive"))
      (node (ref "MOTOR_L_SENSE_OUT") (pin "P$1") (pinfunction "1_P$1") (pintype "passive"))
      (node (ref "R23") (pin "1") (pinfunction "1_1") (pintype "passive"))
    )
    (net (code "73") (name "Net-(MOTOR_L_SENSE_INB-1)") (class "Default")
      (node (ref "MOTOR_L_SENSE_IN") (pin "P$2") (pinfunction "1_P$2") (pintype "passive"))
      (node (ref "MOTOR_L_SENSE_OUT") (pin "P$2") (pinfunction "1_P$2") (pintype "passive"))
      (node (ref "R25") (pin "1") (pinfunction "1_1") (pintype "passive"))
    )
    (net (code "74") (name "Net-(MOTOR_L_SENSE_INC-1)") (class "Default")
      (node (ref "MOTOR_L_SENSE_IN") (pin "P$3") (pinfunction "1_P$3") (pintype "passive"))
      (node (ref "MOTOR_L_SENSE_OUT") (pin "P$3") (pinfunction "1_P$3") (pintype "passive"))
      (node (ref "R27") (pin "1") (pinfunction "1_1") (pintype "passive"))
    )
    (net (code "75") (name "Net-(MOTOR_R_SENSE_INA-1)") (class "Default")
      (node (ref "MOTOR_R_SENSE_IN") (pin "P$1") (pinfunction "1_P$1") (pintype "passive"))
      (node (ref "MOTOR_R_SENSE_OUT") (pin "P$1") (pinfunction "1_P$1") (pintype "passive"))
      (node (ref "R29") (pin "1") (pinfunction "1_1") (pintype "passive"))
    )
    (net (code "76") (name "Net-(MOTOR_R_SENSE_INB-1)") (class "Default")
      (node (ref "MOTOR_R_SENSE_IN") (pin "P$2") (pinfunction "1_P$2") (pintype "passive"))
      (node (ref "MOTOR_R_SENSE_OUT") (pin "P$2") (pinfunction "1_P$2") (pintype "passive"))
      (node (ref "R31") (pin "1") (pinfunction "1_1") (pintype "passive"))
    )
    (net (code "77") (name "Net-(MOTOR_R_SENSE_INC-1)") (class "Default")
      (node (ref "MOTOR_R_SENSE_IN") (pin "P$3") (pinfunction "1_P$3") (pintype "passive"))
      (node (ref "MOTOR_R_SENSE_OUT") (pin "P$3") (pinfunction "1_P$3") (pintype "passive"))
      (node (ref "R33") (pin "1") (pinfunction "1_1") (pintype "passive"))
    )
    (net (code "78") (name "Net-(PCBPOWER-POS)") (class "Default")
      (node (ref "PCBPOWER") (pin "2") (pinfunction "POS_2") (pintype "power_in"))
      (node (ref "PCB_SW") (pin "1") (pinfunction "GND_1") (pintype "power_in"))
    )
    (net (code "79") (name "Net-(PCB_SENSE_INA-1)") (class "Default")
      (node (ref "PCB_SENSE_IN") (pin "P$1") (pinfunction "1_P$1") (pintype "passive"))
      (node (ref "PCB_SENSE_OUT") (pin "P$1") (pinfunction "1_P$1") (pintype "passive"))
      (node (ref "R17") (pin "1") (pinfunction "1_1") (pintype "passive"))
    )
    (net (code "80") (name "Net-(PCB_SENSE_INB-1)") (class "Default")
      (node (ref "PCB_SENSE_IN") (pin "P$2") (pinfunction "1_P$2") (pintype "passive"))
      (node (ref "PCB_SENSE_OUT") (pin "P$2") (pinfunction "1_P$2") (pintype "passive"))
      (node (ref "R19") (pin "1") (pinfunction "1_1") (pintype "passive"))
    )
    (net (code "81") (name "Net-(PCB_SENSE_INC-1)") (class "Default")
      (node (ref "PCB_SENSE_IN") (pin "P$3") (pinfunction "1_P$3") (pintype "passive"))
      (node (ref "PCB_SENSE_OUT") (pin "P$3") (pinfunction "1_P$3") (pintype "passive"))
      (node (ref "R21") (pin "1") (pinfunction "1_1") (pintype "passive"))
    )
    (net (code "82") (name "Net-(PWR-PadA)") (class "Default")
      (node (ref "PWR") (pin "A") (pinfunction "A_A") (pintype "passive"))
      (node (ref "R48") (pin "2") (pinfunction "2_2") (pintype "passive"))
    )
    (net (code "83") (name "Net-(R3-Pad2)") (class "Default")
      (node (ref "R3") (pin "2") (pinfunction "2_2") (pintype "passive"))
      (node (ref "R4") (pin "1") (pinfunction "1_1") (pintype "passive"))
      (node (ref "RASPI_PWR") (pin "3") (pinfunction "3_3") (pintype "bidirectional"))
    )
    (net (code "84") (name "Net-(R5-Pad2)") (class "Default")
      (node (ref "R5") (pin "2") (pinfunction "2_2") (pintype "passive"))
      (node (ref "R6") (pin "1") (pinfunction "1_1") (pintype "passive"))
      (node (ref "RASPI_PWR") (pin "2") (pinfunction "2_2") (pintype "bidirectional"))
    )
    (net (code "85") (name "Net-(R56-Pad1)") (class "Default")
      (node (ref "R56") (pin "1") (pinfunction "1_1") (pintype "passive"))
      (node (ref "RST") (pin "A") (pinfunction "A_A") (pintype "passive"))
    )
    (net (code "86") (name "Net-(RASPI_SW_REG-COMMON(GROUND))") (class "Default")
      (node (ref "R44") (pin "2") (pinfunction "2_2") (pintype "passive"))
      (node (ref "RASPI_SW") (pin "D") (pinfunction "D_D") (pintype "passive"))
      (node (ref "RASPI_SW_REG") (pin "2") (pinfunction "COMMON(GROUND)_2") (pintype "bidirectional"))
    )
    (net (code "87") (name "Net-(RASPI_SW_REG-POSITIVE_OUTPUT)") (class "Default")
      (node (ref "C2") (pin "+") (pinfunction "+_+") (pintype "passive"))
      (node (ref "R3") (pin "1") (pinfunction "1_1") (pintype "passive"))
      (node (ref "R5") (pin "1") (pinfunction "1_1") (pintype "passive"))
      (node (ref "RASPI_PWR") (pin "1") (pinfunction "1_1") (pintype "bidirectional"))
      (node (ref "RASPI_SW_REG") (pin "3") (pinfunction "POSITIVE_OUTPUT_3") (pintype "bidirectional"))
    )
    (net (code "88") (name "Net-(RIGHT_MOTOR-Pad4)") (class "Default")
      (node (ref "RIGHT_MOTOR") (pin "4") (pinfunction "4_4") (pintype "bidirectional"))
      (node (ref "RM_SW") (pin "D") (pinfunction "D_D") (pintype "passive"))
    )
    (net (code "89") (name "PCB_CELL1") (class "Default")
      (node (ref "C8") (pin "1") (pinfunction "1_1") (pintype "passive"))
      (node (ref "IC5") (pin "30") (pinfunction "PA5_30") (pintype "bidirectional"))
      (node (ref "PCB1") (pin "TP") (pinfunction "TP_TP") (pintype "input"))
      (node (ref "R21") (pin "2") (pinfunction "2_2") (pintype "passive"))
      (node (ref "R22") (pin "1") (pinfunction "1_1") (pintype "passive"))
    )
    (net (code "90") (name "PCB_CELL2") (class "Default")
      (node (ref "C7") (pin "1") (pinfunction "1_1") (pintype "passive"))
      (node (ref "IC5") (pin "31") (pinfunction "PA6_31") (pintype "bidirectional"))
      (node (ref "PCB2") (pin "TP") (pinfunction "TP_TP") (pintype "input"))
      (node (ref "R19") (pin "2") (pinfunction "2_2") (pintype "passive"))
      (node (ref "R20") (pin "1") (pinfunction "1_1") (pintype "passive"))
    )
    (net (code "91") (name "PCB_CELL3") (class "Default")
      (node (ref "C6") (pin "1") (pinfunction "1_1") (pintype "passive"))
      (node (ref "IC5") (pin "32") (pinfunction "PA7_32") (pintype "bidirectional"))
      (node (ref "PCB3") (pin "TP") (pinfunction "TP_TP") (pintype "input"))
      (node (ref "R17") (pin "2") (pinfunction "2_2") (pintype "passive"))
      (node (ref "R18") (pin "1") (pinfunction "1_1") (pintype "passive"))
    )
    (net (code "92") (name "RASPI_MOS") (class "Default")
      (node (ref "IC5") (pin "70") (pinfunction "PA11_70") (pintype "bidirectional"))
      (node (ref "R16") (pin "2") (pinfunction "2_2") (pintype "passive"))
      (node (ref "RASPI_SW") (pin "G") (pinfunction "G_G") (pintype "passive"))
    )
    (net (code "93") (name "R_MOS") (class "Default")
      (node (ref "IC5") (pin "68") (pinfunction "PA9_68") (pintype "bidirectional"))
      (node (ref "R53") (pin "2") (pinfunction "2_2") (pintype "passive"))
      (node (ref "RM_SW") (pin "G") (pinfunction "G_G") (pintype "passive"))
    )
    (net (code "94") (name "R_PWM") (class "Default")
      (node (ref "IC5") (pin "64") (pinfunction "PC7_64") (pintype "bidirectional"))
      (node (ref "RIGHT_MOTOR") (pin "1") (pinfunction "1_1") (pintype "bidirectional"))
    )
    (net (code "95") (name "SWCLK") (class "Default")
      (node (ref "IC5") (pin "76") (pinfunction "PA14_76") (pintype "bidirectional"))
      (node (ref "STLINK") (pin "2") (pinfunction "2_2") (pintype "passive"))
    )
    (net (code "96") (name "SWDIO") (class "Default")
      (node (ref "IC5") (pin "72") (pinfunction "PA13_72") (pintype "bidirectional"))
      (node (ref "STLINK") (pin "4") (pinfunction "4_4") (pintype "passive"))
    )
    (net (code "97") (name "SWO") (class "Default")
      (node (ref "IC5") (pin "89") (pinfunction "PB3_89") (pintype "bidirectional"))
      (node (ref "STLINK") (pin "6") (pinfunction "6_6") (pintype "passive"))
    )
    (net (code "98") (name "VBAT") (class "Default")
      (node (ref "CONV_SW_REG") (pin "1") (pinfunction "POSITIVE_INPUT_1") (pintype "bidirectional"))
      (node (ref "LTE_SW_REG") (pin "1") (pinfunction "POSITIVE_INPUT_1") (pintype "bidirectional"))
      (node (ref "MICRO_SW_REG") (pin "1") (pinfunction "POSITIVE_INPUT_1") (pintype "bidirectional"))
      (node (ref "PCB_SW") (pin "2") (pinfunction "POS_2") (pintype "power_in"))
      (node (ref "R16") (pin "1") (pinfunction "1_1") (pintype "passive"))
      (node (ref "R43") (pin "1") (pinfunction "1_1") (pintype "passive"))
      (node (ref "R44") (pin "1") (pinfunction "1_1") (pintype "passive"))
      (node (ref "RASPI_SW_REG") (pin "1") (pinfunction "POSITIVE_INPUT_1") (pintype "bidirectional"))
    )
    (net (code "99") (name "VCC") (class "Default")
      (node (ref "C13") (pin "2") (pinfunction "2_2") (pintype "passive"))
      (node (ref "C14") (pin "1") (pinfunction "1_1") (pintype "passive"))
      (node (ref "C18") (pin "1") (pinfunction "1_1") (pintype "passive"))
      (node (ref "C25") (pin "1") (pinfunction "1_1") (pintype "passive"))
      (node (ref "C26") (pin "1") (pinfunction "1_1") (pintype "passive"))
      (node (ref "C38") (pin "2") (pinfunction "2_2") (pintype "passive"))
      (node (ref "C4") (pin "+") (pinfunction "+_+") (pintype "passive"))
      (node (ref "C41") (pin "1") (pinfunction "1_1") (pintype "passive"))
      (node (ref "C42") (pin "1") (pinfunction "1_1") (pintype "passive"))
      (node (ref "C43") (pin "1") (pinfunction "1_1") (pintype "passive"))
      (node (ref "C44") (pin "1") (pinfunction "1_1") (pintype "passive"))
      (node (ref "C45") (pin "1") (pinfunction "1_1") (pintype "passive"))
      (node (ref "COMPASS_HEADER") (pin "1") (pinfunction "1_1") (pintype "passive"))
      (node (ref "COMPASS_HEADER") (pin "2") (pinfunction "2_2") (pintype "passive"))
      (node (ref "IC5") (pin "100") (pinfunction "VDD_100") (pintype "power_in"))
      (node (ref "IC5") (pin "11") (pinfunction "VDD_11") (pintype "power_in"))
      (node (ref "IC5") (pin "19") (pinfunction "VDD_19") (pintype "power_in"))
      (node (ref "IC5") (pin "28") (pinfunction "VDD_28") (pintype "power_in"))
      (node (ref "IC5") (pin "50") (pinfunction "VDD_50") (pintype "power_in"))
      (node (ref "IC5") (pin "6") (pinfunction "VBAT_6") (pintype "power_in"))
      (node (ref "IC5") (pin "75") (pinfunction "VDD_75") (pintype "power_in"))
      (node (ref "JP2") (pin "1") (pinfunction "1_1") (pintype "passive"))
      (node (ref "JP4") (pin "1") (pinfunction "1_1") (pintype "passive"))
      (node (ref "JP5") (pin "2") (pinfunction "2_2") (pintype "passive"))
      (node (ref "L1") (pin "2") (pinfunction "2_2") (pintype "passive"))
      (node (ref "MICRO_REG") (pin "2") (pinfunction "VOUT_2") (pintype "output"))
      (node (ref "R12") (pin "1") (pinfunction "1_1") (pintype "passive"))
      (node (ref "R14") (pin "1") (pinfunction "1_1") (pintype "passive"))
      (node (ref "R36") (pin "2") (pinfunction "2_2") (pintype "passive"))
      (node (ref "R47") (pin "2") (pinfunction "2_2") (pintype "passive"))
      (node (ref "R48") (pin "1") (pinfunction "1_1") (pintype "passive"))
      (node (ref "R49") (pin "2") (pinfunction "2_2") (pintype "passive"))
      (node (ref "R52") (pin "1") (pinfunction "1_1") (pintype "passive"))
      (node (ref "R54") (pin "2") (pinfunction "2_2") (pintype "passive"))
      (node (ref "R55") (pin "2") (pinfunction "2_2") (pintype "passive"))
      (node (ref "SPI_CMP") (pin "15") (pinfunction "VDD_15") (pintype "bidirectional"))
      (node (ref "SPI_CMP") (pin "8") (pinfunction "VDD_IO_8") (pintype "bidirectional"))
      (node (ref "STLINK") (pin "1") (pinfunction "1_1") (pintype "passive"))
    )
    (net (code "100") (name "VDD") (class "Default")
      (node (ref "C10") (pin "1") (pinfunction "1_1") (pintype "passive"))
      (node (ref "C3") (pin "+") (pinfunction "+_+") (pintype "passive"))
      (node (ref "LASER_HEADER") (pin "10") (pinfunction "10_10") (pintype "passive"))
      (node (ref "LASER_HEADER") (pin "2") (pinfunction "2_2") (pintype "passive"))
      (node (ref "LASER_HEADER") (pin "4") (pinfunction "4_4") (pintype "passive"))
      (node (ref "LASER_HEADER") (pin "6") (pinfunction "6_6") (pintype "passive"))
      (node (ref "LASER_HEADER") (pin "8") (pinfunction "8_8") (pintype "passive"))
      (node (ref "LDR_HEADER") (pin "1") (pinfunction "1_1") (pintype "passive"))
      (node (ref "LDR_HEADER") (pin "3") (pinfunction "3_3") (pintype "passive"))
      (node (ref "LDR_HEADER") (pin "5") (pinfunction "5_5") (pintype "passive"))
      (node (ref "LDR_HEADER") (pin "7") (pinfunction "7_7") (pintype "passive"))
      (node (ref "LDR_HEADER") (pin "9") (pinfunction "9_9") (pintype "passive"))
      (node (ref "MICRO_REG") (pin "3") (pinfunction "VIN_3") (pintype "input"))
      (node (ref "MICRO_SW_REG") (pin "3") (pinfunction "POSITIVE_OUTPUT_3") (pintype "bidirectional"))
    )
    (net (code "101") (name "VDD_BREAKOUT") (class "Default")
      (node (ref "C11") (pin "1") (pinfunction "1_1") (pintype "passive"))
      (node (ref "C12") (pin "1") (pinfunction "1_1") (pintype "passive"))
      (node (ref "CMP_BRKOUT") (pin "1") (pinfunction "1_1") (pintype "passive"))
      (node (ref "CMP_BRKOUT") (pin "2") (pinfunction "2_2") (pintype "passive"))
      (node (ref "IC3") (pin "11") (pinfunction "A1_11") (pintype "bidirectional"))
      (node (ref "IC3") (pin "12") (pinfunction "A0_12") (pintype "bidirectional"))
      (node (ref "IC3") (pin "15") (pinfunction "VDD_15") (pintype "bidirectional"))
      (node (ref "IC3") (pin "2") (pinfunction "SENB/CS_2") (pintype "bidirectional"))
      (node (ref "IC3") (pin "8") (pinfunction "VDD_IO_8") (pintype "bidirectional"))
      (node (ref "R10") (pin "1") (pinfunction "1_1") (pintype "passive"))
      (node (ref "R9") (pin "1") (pinfunction "1_1") (pintype "passive"))
    )
    (net (code "102") (name "unconnected-(ESP8266_HEADER-Pad6)") (class "Default")
      (node (ref "ESP8266_HEADER") (pin "6") (pinfunction "6_6") (pintype "passive"))
    )
    (net (code "103") (name "unconnected-(ESP_DEBUG-Pad2)") (class "Default")
      (node (ref "ESP_DEBUG") (pin "2") (pinfunction "2_2") (pintype "passive"))
    )
    (net (code "104") (name "unconnected-(ESP_DEBUG-Pad6)") (class "Default")
      (node (ref "ESP_DEBUG") (pin "6") (pinfunction "6_6") (pintype "passive"))
    )
    (net (code "105") (name "unconnected-(GPS_DEBUG-Pad2)") (class "Default")
      (node (ref "GPS_DEBUG") (pin "2") (pinfunction "2_2") (pintype "passive"))
    )
    (net (code "106") (name "unconnected-(GPS_DEBUG-Pad6)") (class "Default")
      (node (ref "GPS_DEBUG") (pin "6") (pinfunction "6_6") (pintype "passive"))
    )
    (net (code "107") (name "unconnected-(IC3-MISO-Pad6)") (class "Default")
      (node (ref "IC3") (pin "6") (pinfunction "MISO_6") (pintype "bidirectional"))
    )
    (net (code "108") (name "unconnected-(IC3-THERMAL_PAD-Pad17)") (class "Default")
      (node (ref "IC3") (pin "17") (pinfunction "THERMAL_PAD_17") (pintype "bidirectional"))
    )
    (net (code "109") (name "unconnected-(IC5-PB4-Pad90)") (class "Default")
      (node (ref "IC5") (pin "90") (pinfunction "PB4_90") (pintype "bidirectional"))
    )
    (net (code "110") (name "unconnected-(IC5-PB5-Pad91)") (class "Default")
      (node (ref "IC5") (pin "91") (pinfunction "PB5_91") (pintype "bidirectional"))
    )
    (net (code "111") (name "unconnected-(IC5-PB12-Pad51)") (class "Default")
      (node (ref "IC5") (pin "51") (pinfunction "PB12_51") (pintype "bidirectional"))
    )
    (net (code "112") (name "unconnected-(IC5-PC4-Pad33)") (class "Default")
      (node (ref "IC5") (pin "33") (pinfunction "PC4_33") (pintype "bidirectional"))
    )
    (net (code "113") (name "unconnected-(IC5-PC5-Pad34)") (class "Default")
      (node (ref "IC5") (pin "34") (pinfunction "PC5_34") (pintype "bidirectional"))
    )
    (net (code "114") (name "unconnected-(IC5-PC8-Pad65)") (class "Default")
      (node (ref "IC5") (pin "65") (pinfunction "PC8_65") (pintype "bidirectional"))
    )
    (net (code "115") (name "unconnected-(IC5-PC9-Pad66)") (class "Default")
      (node (ref "IC5") (pin "66") (pinfunction "PC9_66") (pintype "bidirectional"))
    )
    (net (code "116") (name "unconnected-(IC5-PC10-Pad78)") (class "Default")
      (node (ref "IC5") (pin "78") (pinfunction "PC10_78") (pintype "bidirectional"))
    )
    (net (code "117") (name "unconnected-(IC5-PC11-Pad79)") (class "Default")
      (node (ref "IC5") (pin "79") (pinfunction "PC11_79") (pintype "bidirectional"))
    )
    (net (code "118") (name "unconnected-(IC5-PC12-Pad80)") (class "Default")
      (node (ref "IC5") (pin "80") (pinfunction "PC12_80") (pintype "bidirectional"))
    )
    (net (code "119") (name "unconnected-(IC5-PC13-Pad7)") (class "Default")
      (node (ref "IC5") (pin "7") (pinfunction "PC13_7") (pintype "bidirectional"))
    )
    (net (code "120") (name "unconnected-(IC5-PC14-Pad8)") (class "Default")
      (node (ref "IC5") (pin "8") (pinfunction "PC14_8") (pintype "bidirectional"))
    )
    (net (code "121") (name "unconnected-(IC5-PC15-Pad9)") (class "Default")
      (node (ref "IC5") (pin "9") (pinfunction "PC15_9") (pintype "bidirectional"))
    )
    (net (code "122") (name "unconnected-(IC5-PD0-Pad81)") (class "Default")
      (node (ref "IC5") (pin "81") (pinfunction "PD0_81") (pintype "bidirectional"))
    )
    (net (code "123") (name "unconnected-(IC5-PD1-Pad82)") (class "Default")
      (node (ref "IC5") (pin "82") (pinfunction "PD1_82") (pintype "bidirectional"))
    )
    (net (code "124") (name "unconnected-(IC5-PD2-Pad83)") (class "Default")
      (node (ref "IC5") (pin "83") (pinfunction "PD2_83") (pintype "bidirectional"))
    )
    (net (code "125") (name "unconnected-(IC5-PD3-Pad84)") (class "Default")
      (node (ref "IC5") (pin "84") (pinfunction "PD3_84") (pintype "bidirectional"))
    )
    (net (code "126") (name "unconnected-(IC5-PD4-Pad85)") (class "Default")
      (node (ref "IC5") (pin "85") (pinfunction "PD4_85") (pintype "bidirectional"))
    )
    (net (code "127") (name "unconnected-(IC5-PD5-Pad86)") (class "Default")
      (node (ref "IC5") (pin "86") (pinfunction "PD5_86") (pintype "bidirectional"))
    )
    (net (code "128") (name "unconnected-(IC5-PD6-Pad87)") (class "Default")
      (node (ref "IC5") (pin "87") (pinfunction "PD6_87") (pintype "bidirectional"))
    )
    (net (code "129") (name "unconnected-(IC5-PD7-Pad88)") (class "Default")
      (node (ref "IC5") (pin "88") (pinfunction "PD7_88") (pintype "bidirectional"))
    )
    (net (code "130") (name "unconnected-(IC5-PD8-Pad55)") (class "Default")
      (node (ref "IC5") (pin "55") (pinfunction "PD8_55") (pintype "bidirectional"))
    )
    (net (code "131") (name "unconnected-(IC5-PD9-Pad56)") (class "Default")
      (node (ref "IC5") (pin "56") (pinfunction "PD9_56") (pintype "bidirectional"))
    )
    (net (code "132") (name "unconnected-(IC5-PD10-Pad57)") (class "Default")
      (node (ref "IC5") (pin "57") (pinfunction "PD10_57") (pintype "bidirectional"))
    )
    (net (code "133") (name "unconnected-(IC5-PD11-Pad58)") (class "Default")
      (node (ref "IC5") (pin "58") (pinfunction "PD11_58") (pintype "bidirectional"))
    )
    (net (code "134") (name "unconnected-(IC5-PD12-Pad59)") (class "Default")
      (node (ref "IC5") (pin "59") (pinfunction "PD12_59") (pintype "bidirectional"))
    )
    (net (code "135") (name "unconnected-(IC5-PD13-Pad60)") (class "Default")
      (node (ref "IC5") (pin "60") (pinfunction "PD13_60") (pintype "bidirectional"))
    )
    (net (code "136") (name "unconnected-(IC5-PD14-Pad61)") (class "Default")
      (node (ref "IC5") (pin "61") (pinfunction "PD14_61") (pintype "bidirectional"))
    )
    (net (code "137") (name "unconnected-(IC5-PE0-Pad97)") (class "Default")
      (node (ref "IC5") (pin "97") (pinfunction "PE0_97") (pintype "bidirectional"))
    )
    (net (code "138") (name "unconnected-(IC5-PE1-Pad98)") (class "Default")
      (node (ref "IC5") (pin "98") (pinfunction "PE1_98") (pintype "bidirectional"))
    )
    (net (code "139") (name "unconnected-(IC5-PE2-Pad1)") (class "Default")
      (node (ref "IC5") (pin "1") (pinfunction "PE2_1") (pintype "bidirectional"))
    )
    (net (code "140") (name "unconnected-(IC5-PE3-Pad2)") (class "Default")
      (node (ref "IC5") (pin "2") (pinfunction "PE3_2") (pintype "bidirectional"))
    )
    (net (code "141") (name "unconnected-(IC5-PE4-Pad3)") (class "Default")
      (node (ref "IC5") (pin "3") (pinfunction "PE4_3") (pintype "bidirectional"))
    )
    (net (code "142") (name "unconnected-(IC5-PE5-Pad4)") (class "Default")
      (node (ref "IC5") (pin "4") (pinfunction "PE5_4") (pintype "bidirectional"))
    )
    (net (code "143") (name "unconnected-(IC5-PE6-Pad5)") (class "Default")
      (node (ref "IC5") (pin "5") (pinfunction "PE6_5") (pintype "bidirectional"))
    )
    (net (code "144") (name "unconnected-(IC5-PE11-Pad42)") (class "Default")
      (node (ref "IC5") (pin "42") (pinfunction "PE11_42") (pintype "bidirectional"))
    )
    (net (code "145") (name "unconnected-(IC5-PE12-Pad43)") (class "Default")
      (node (ref "IC5") (pin "43") (pinfunction "PE12_43") (pintype "bidirectional"))
    )
    (net (code "146") (name "unconnected-(IC5-PE13-Pad44)") (class "Default")
      (node (ref "IC5") (pin "44") (pinfunction "PE13_44") (pintype "bidirectional"))
    )
    (net (code "147") (name "unconnected-(IC5-PE14-Pad45)") (class "Default")
      (node (ref "IC5") (pin "45") (pinfunction "PE14_45") (pintype "bidirectional"))
    )
    (net (code "148") (name "unconnected-(IC5-PE15-Pad46)") (class "Default")
      (node (ref "IC5") (pin "46") (pinfunction "PE15_46") (pintype "bidirectional"))
    )
    (net (code "149") (name "unconnected-(LEFT_MOTOR-Pad2)") (class "Default")
      (node (ref "LEFT_MOTOR") (pin "2") (pinfunction "2_2") (pintype "bidirectional"))
    )
    (net (code "150") (name "unconnected-(RIGHT_MOTOR-Pad2)") (class "Default")
      (node (ref "RIGHT_MOTOR") (pin "2") (pinfunction "2_2") (pintype "bidirectional"))
    )
    (net (code "151") (name "unconnected-(SPI_CMP-THERMAL_PAD-Pad17)") (class "Default")
      (node (ref "SPI_CMP") (pin "17") (pinfunction "THERMAL_PAD_17") (pintype "bidirectional"))
    )
  )
)
